# TC_board.net
KiCad netlist of a schematic drawn in EAGLE
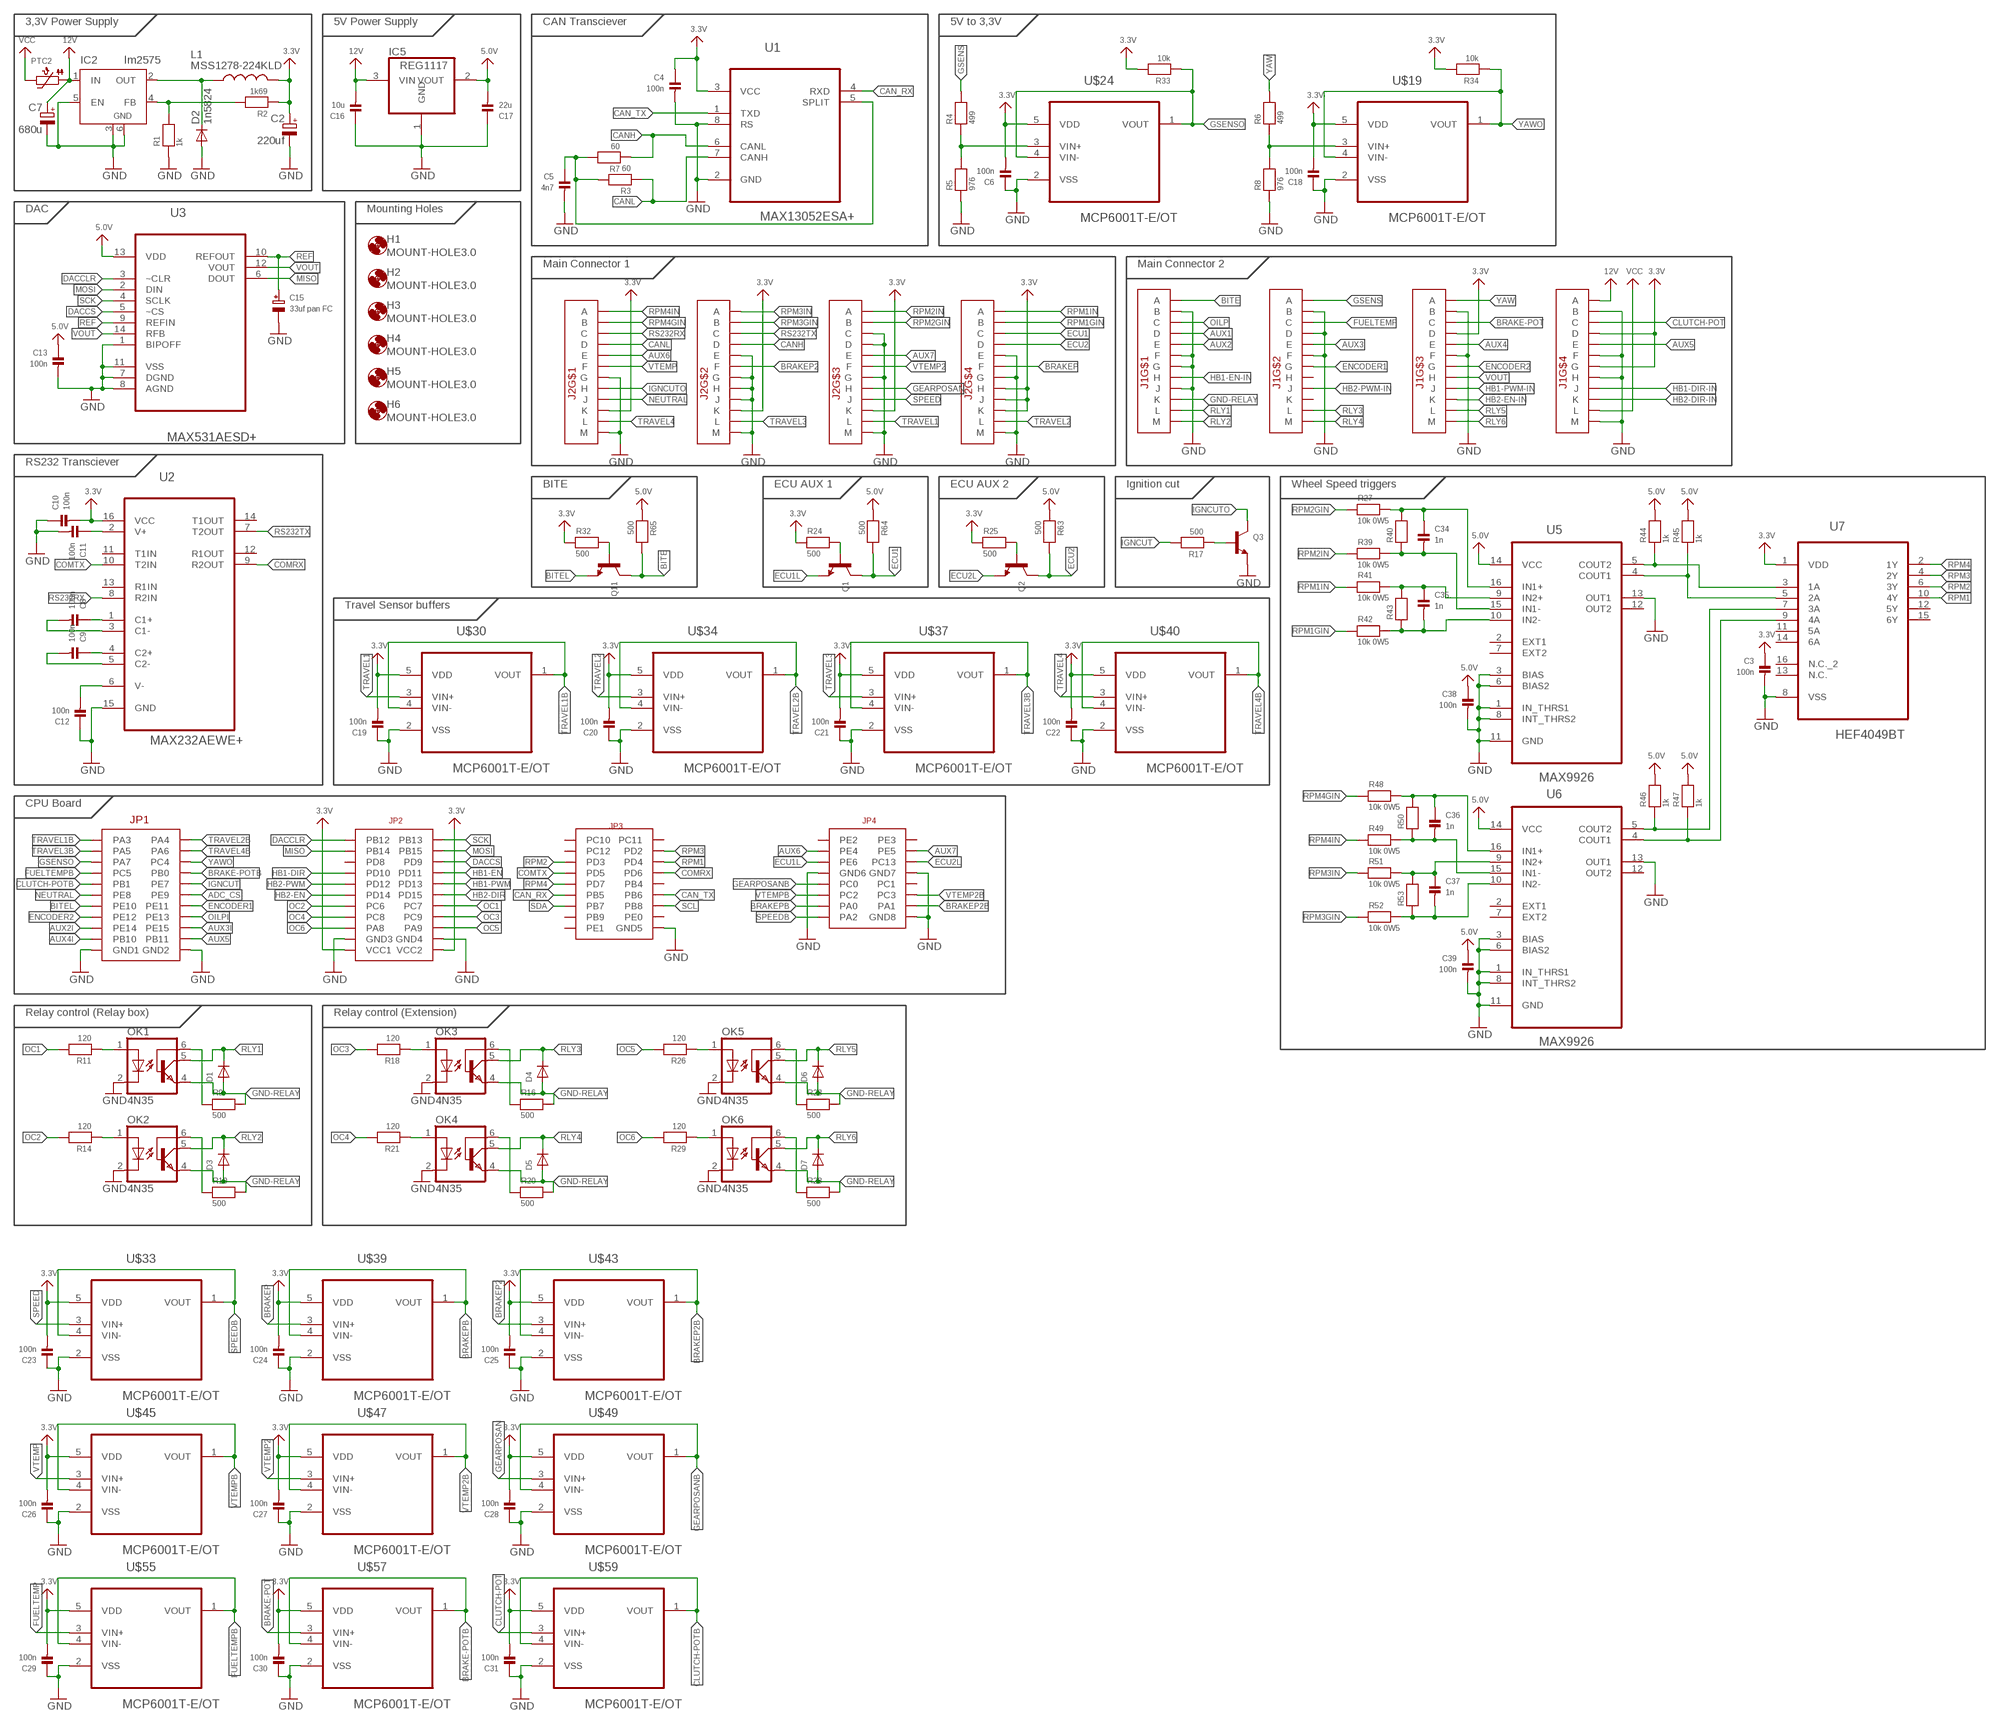
[diagram p0: schematic, sheet 1, part 1 of 2]
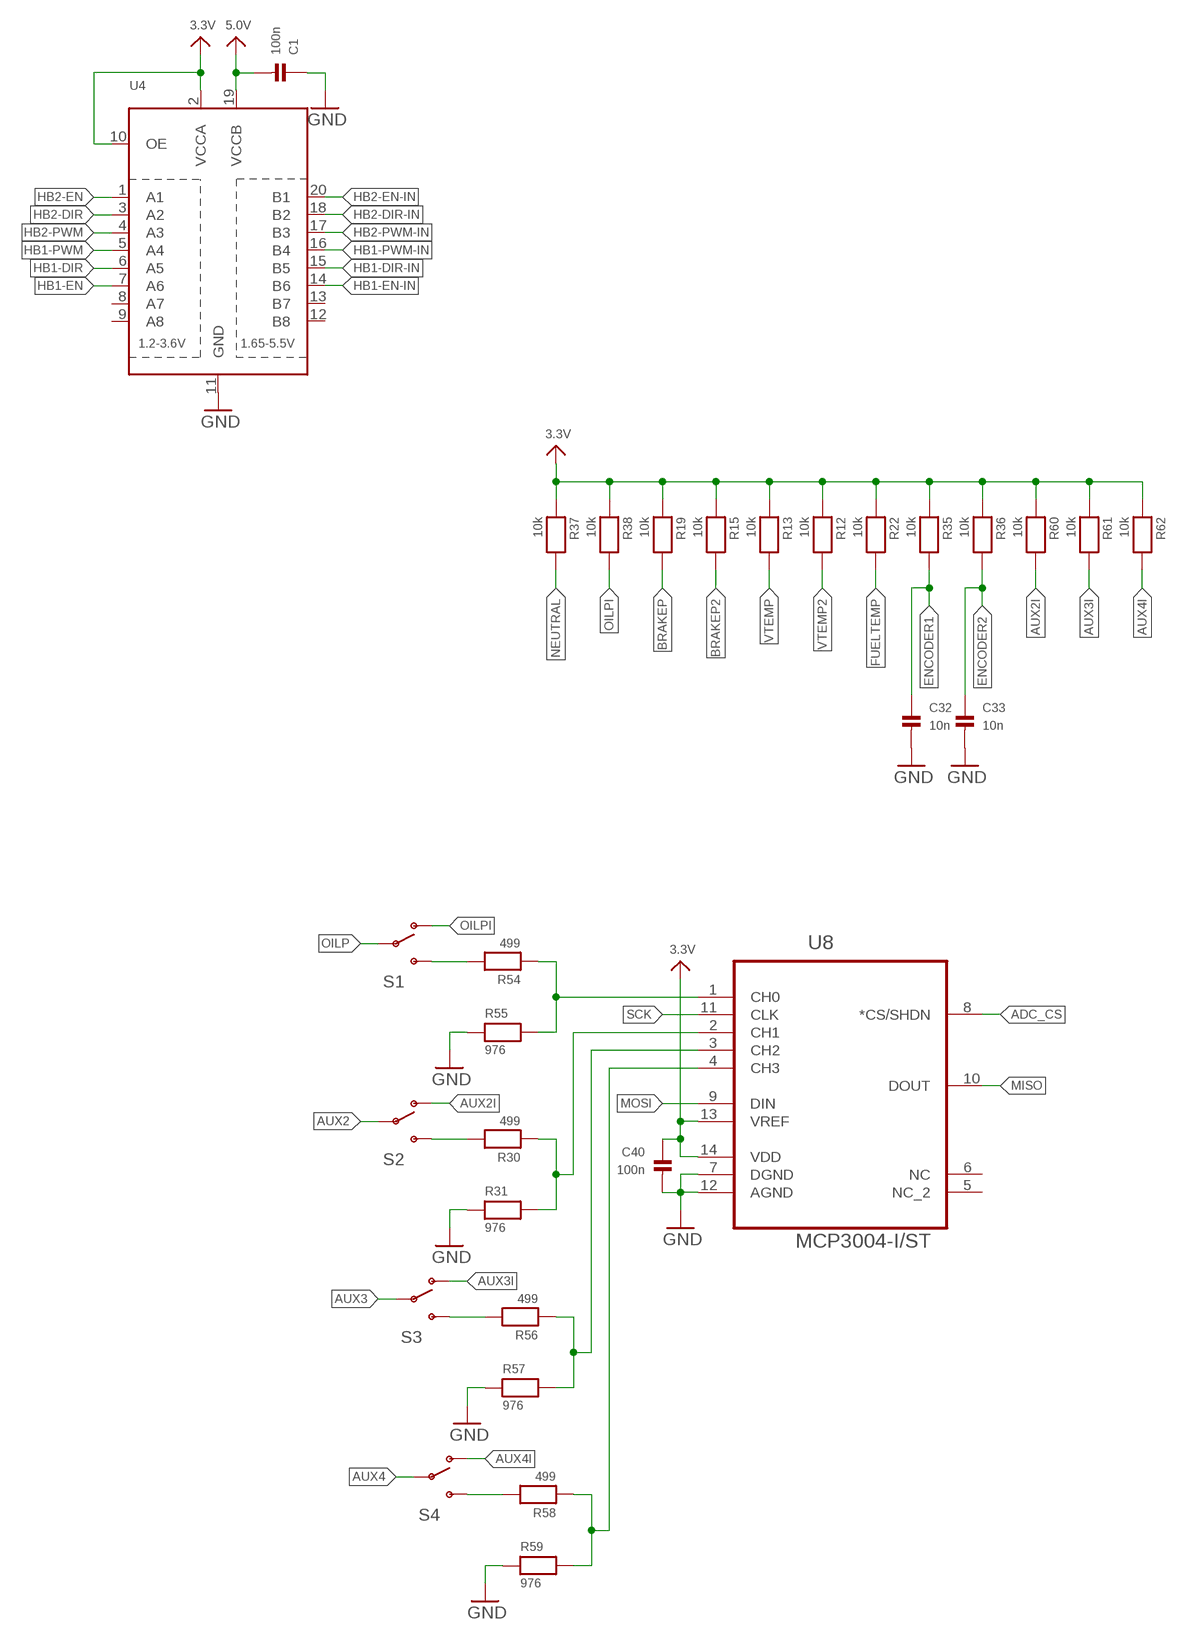
[diagram p1: schematic, sheet 1, part 2 of 2]

(export (version "E")
  (design (tool "Eeschema 10.0.6"))
  (components
    (comp (ref "C1")
      (value "100n")
      (footprint "eagle-import:_0603")
      (libsource (lib "eagle-import") (part "CAP_CERAMIC_0603"))
    )
    (comp (ref "C2")
      (value "220uf")
      (footprint "eagle-import:E3,5-8")
      (libsource (lib "eagle-import") (part "CPOL-EUE3.5-8"))
    )
    (comp (ref "C3")
      (value "100n")
      (footprint "eagle-import:_0603")
      (libsource (lib "eagle-import") (part "CAP_CERAMIC_0603"))
    )
    (comp (ref "C4")
      (value "100n")
      (footprint "eagle-import:_0603")
      (libsource (lib "eagle-import") (part "CAP_CERAMIC_0603"))
    )
    (comp (ref "C5")
      (value "4n7")
      (footprint "eagle-import:_0603")
      (libsource (lib "eagle-import") (part "CAP_CERAMIC_0603"))
    )
    (comp (ref "C6")
      (value "100n")
      (footprint "eagle-import:_0603")
      (libsource (lib "eagle-import") (part "CAP_CERAMIC_0603"))
    )
    (comp (ref "C7")
      (value "680u")
      (footprint "eagle-import:E5-10,5")
      (libsource (lib "eagle-import") (part "CPOL-EUE5-10.5"))
    )
    (comp (ref "C8")
      (value "100n")
      (footprint "eagle-import:_0603")
      (libsource (lib "eagle-import") (part "CAP_CERAMIC_0603"))
    )
    (comp (ref "C9")
      (value "100n")
      (footprint "eagle-import:_0603")
      (libsource (lib "eagle-import") (part "CAP_CERAMIC_0603"))
    )
    (comp (ref "C10")
      (value "100n")
      (footprint "eagle-import:_0603")
      (libsource (lib "eagle-import") (part "CAP_CERAMIC_0603"))
    )
    (comp (ref "C11")
      (value "100n")
      (footprint "eagle-import:_0603")
      (libsource (lib "eagle-import") (part "CAP_CERAMIC_0603"))
    )
    (comp (ref "C12")
      (value "100n")
      (footprint "eagle-import:_0603")
      (libsource (lib "eagle-import") (part "CAP_CERAMIC_0603"))
    )
    (comp (ref "C13")
      (value "100n")
      (footprint "eagle-import:_0603")
      (libsource (lib "eagle-import") (part "CAP_CERAMIC_0603"))
    )
    (comp (ref "C15")
      (value "33uf pan FC")
      (footprint "eagle-import:PANASONIC_D")
      (libsource (lib "eagle-import") (part "CAP_ELECTROLYTICPANASONIC_D"))
    )
    (comp (ref "C16")
      (value "10u")
      (footprint "eagle-import:_0805")
      (libsource (lib "eagle-import") (part "CAP_CERAMIC_0805"))
    )
    (comp (ref "C17")
      (value "22u")
      (footprint "eagle-import:_0805")
      (libsource (lib "eagle-import") (part "CAP_CERAMIC_0805"))
    )
    (comp (ref "C18")
      (value "100n")
      (footprint "eagle-import:_0603")
      (libsource (lib "eagle-import") (part "CAP_CERAMIC_0603"))
    )
    (comp (ref "C19")
      (value "100n")
      (footprint "eagle-import:_0603")
      (libsource (lib "eagle-import") (part "CAP_CERAMIC_0603"))
    )
    (comp (ref "C20")
      (value "100n")
      (footprint "eagle-import:_0603")
      (libsource (lib "eagle-import") (part "CAP_CERAMIC_0603"))
    )
    (comp (ref "C21")
      (value "100n")
      (footprint "eagle-import:_0603")
      (libsource (lib "eagle-import") (part "CAP_CERAMIC_0603"))
    )
    (comp (ref "C22")
      (value "100n")
      (footprint "eagle-import:_0603")
      (libsource (lib "eagle-import") (part "CAP_CERAMIC_0603"))
    )
    (comp (ref "C23")
      (value "100n")
      (footprint "eagle-import:_0603")
      (libsource (lib "eagle-import") (part "CAP_CERAMIC_0603"))
    )
    (comp (ref "C24")
      (value "100n")
      (footprint "eagle-import:_0603")
      (libsource (lib "eagle-import") (part "CAP_CERAMIC_0603"))
    )
    (comp (ref "C25")
      (value "100n")
      (footprint "eagle-import:_0603")
      (libsource (lib "eagle-import") (part "CAP_CERAMIC_0603"))
    )
    (comp (ref "C26")
      (value "100n")
      (footprint "eagle-import:_0603")
      (libsource (lib "eagle-import") (part "CAP_CERAMIC_0603"))
    )
    (comp (ref "C27")
      (value "100n")
      (footprint "eagle-import:_0603")
      (libsource (lib "eagle-import") (part "CAP_CERAMIC_0603"))
    )
    (comp (ref "C28")
      (value "100n")
      (footprint "eagle-import:_0603")
      (libsource (lib "eagle-import") (part "CAP_CERAMIC_0603"))
    )
    (comp (ref "C29")
      (value "100n")
      (footprint "eagle-import:_0603")
      (libsource (lib "eagle-import") (part "CAP_CERAMIC_0603"))
    )
    (comp (ref "C30")
      (value "100n")
      (footprint "eagle-import:_0603")
      (libsource (lib "eagle-import") (part "CAP_CERAMIC_0603"))
    )
    (comp (ref "C31")
      (value "100n")
      (footprint "eagle-import:_0603")
      (libsource (lib "eagle-import") (part "CAP_CERAMIC_0603"))
    )
    (comp (ref "C32")
      (value "10n")
      (footprint "eagle-import:_0603")
      (libsource (lib "eagle-import") (part "CAP_CERAMIC_0603"))
    )
    (comp (ref "C33")
      (value "10n")
      (footprint "eagle-import:_0603")
      (libsource (lib "eagle-import") (part "CAP_CERAMIC_0603"))
    )
    (comp (ref "C34")
      (value "1n")
      (footprint "eagle-import:_0603")
      (libsource (lib "eagle-import") (part "CAP_CERAMIC_0603"))
    )
    (comp (ref "C35")
      (value "1n")
      (footprint "eagle-import:_0603")
      (libsource (lib "eagle-import") (part "CAP_CERAMIC_0603"))
    )
    (comp (ref "C36")
      (value "1n")
      (footprint "eagle-import:_0603")
      (libsource (lib "eagle-import") (part "CAP_CERAMIC_0603"))
    )
    (comp (ref "C37")
      (value "1n")
      (footprint "eagle-import:_0603")
      (libsource (lib "eagle-import") (part "CAP_CERAMIC_0603"))
    )
    (comp (ref "C38")
      (value "100n")
      (footprint "eagle-import:_0603")
      (libsource (lib "eagle-import") (part "CAP_CERAMIC_0603"))
    )
    (comp (ref "C39")
      (value "100n")
      (footprint "eagle-import:_0603")
      (libsource (lib "eagle-import") (part "CAP_CERAMIC_0603"))
    )
    (comp (ref "C40")
      (value "100n")
      (footprint "eagle-import:_0603")
      (libsource (lib "eagle-import") (part "CAP_CERAMIC_0603"))
    )
    (comp (ref "D1")
      (value "DIODESOD-323F")
      (footprint "eagle-import:SOD-323F")
      (libsource (lib "eagle-import") (part "DIODESOD-323F"))
    )
    (comp (ref "D2")
      (value "1n5824")
      (footprint "eagle-import:DO201-15")
      (libsource (lib "eagle-import") (part "1N5400"))
    )
    (comp (ref "D3")
      (value "DIODESOD-323F")
      (footprint "eagle-import:SOD-323F")
      (libsource (lib "eagle-import") (part "DIODESOD-323F"))
    )
    (comp (ref "D4")
      (value "DIODESOD-323F")
      (footprint "eagle-import:SOD-323F")
      (libsource (lib "eagle-import") (part "DIODESOD-323F"))
    )
    (comp (ref "D5")
      (value "DIODESOD-323F")
      (footprint "eagle-import:SOD-323F")
      (libsource (lib "eagle-import") (part "DIODESOD-323F"))
    )
    (comp (ref "D6")
      (value "DIODESOD-323F")
      (footprint "eagle-import:SOD-323F")
      (libsource (lib "eagle-import") (part "DIODESOD-323F"))
    )
    (comp (ref "D7")
      (value "DIODESOD-323F")
      (footprint "eagle-import:SOD-323F")
      (libsource (lib "eagle-import") (part "DIODESOD-323F"))
    )
    (comp (ref "H1")
      (value "MOUNT-HOLE3.0")
      (footprint "eagle-import:3,0")
      (libsource (lib "eagle-import") (part "MOUNT-HOLE3.0"))
    )
    (comp (ref "H2")
      (value "MOUNT-HOLE3.0")
      (footprint "eagle-import:3,0")
      (libsource (lib "eagle-import") (part "MOUNT-HOLE3.0"))
    )
    (comp (ref "H3")
      (value "MOUNT-HOLE3.0")
      (footprint "eagle-import:3,0")
      (libsource (lib "eagle-import") (part "MOUNT-HOLE3.0"))
    )
    (comp (ref "H4")
      (value "MOUNT-HOLE3.0")
      (footprint "eagle-import:3,0")
      (libsource (lib "eagle-import") (part "MOUNT-HOLE3.0"))
    )
    (comp (ref "H5")
      (value "MOUNT-HOLE3.0")
      (footprint "eagle-import:3,0")
      (libsource (lib "eagle-import") (part "MOUNT-HOLE3.0"))
    )
    (comp (ref "H6")
      (value "MOUNT-HOLE3.0")
      (footprint "eagle-import:3,0")
      (libsource (lib "eagle-import") (part "MOUNT-HOLE3.0"))
    )
    (comp (ref "IC2")
      (value "lm2575")
      (footprint "eagle-import:TO263-5")
      (libsource (lib "eagle-import") (part "LM2596S"))
    )
    (comp (ref "IC5")
      (value "REG1117")
      (footprint "eagle-import:SOT223")
      (libsource (lib "eagle-import") (part "REG1117"))
    )
    (comp (ref "J1")
      (value "CON1")
      (footprint "eagle-import:AUTOCONNECTOR")
      (libsource (lib "eagle-import") (part "AUTOCONNECTOR"))
    )
    (comp (ref "J2")
      (value "CON1")
      (footprint "eagle-import:AUTOCONNECTOR")
      (libsource (lib "eagle-import") (part "AUTOCONNECTOR"))
    )
    (comp (ref "L1")
      (value "MSS1278-224KLD")
      (footprint "eagle-import:CDRH125")
      (libsource (lib "eagle-import") (part "INDUCTORPWR"))
    )
    (comp (ref "OK1")
      (value "4N35")
      (footprint "eagle-import:DIL06")
      (fields (field (name "MF") "FAIRCHILD SEMICONDUCTOR"))
      (libsource (lib "eagle-import") (part "4N35"))
    )
    (comp (ref "OK2")
      (value "4N35")
      (footprint "eagle-import:DIL06")
      (fields (field (name "MF") "FAIRCHILD SEMICONDUCTOR"))
      (libsource (lib "eagle-import") (part "4N35"))
    )
    (comp (ref "OK3")
      (value "4N35")
      (footprint "eagle-import:DIL06")
      (fields (field (name "MF") "FAIRCHILD SEMICONDUCTOR"))
      (libsource (lib "eagle-import") (part "4N35"))
    )
    (comp (ref "OK4")
      (value "4N35")
      (footprint "eagle-import:DIL06")
      (fields (field (name "MF") "FAIRCHILD SEMICONDUCTOR"))
      (libsource (lib "eagle-import") (part "4N35"))
    )
    (comp (ref "OK5")
      (value "4N35")
      (footprint "eagle-import:DIL06")
      (fields (field (name "MF") "FAIRCHILD SEMICONDUCTOR"))
      (libsource (lib "eagle-import") (part "4N35"))
    )
    (comp (ref "OK6")
      (value "4N35")
      (footprint "eagle-import:DIL06")
      (fields (field (name "MF") "FAIRCHILD SEMICONDUCTOR"))
      (libsource (lib "eagle-import") (part "4N35"))
    )
    (comp (ref "PTC2")
      (value "PTC1812")
      (footprint "eagle-import:PTC1812")
      (libsource (lib "eagle-import") (part "PTC1812"))
    )
    (comp (ref "Q1")
      (value "TRANSISTOR_NPNWIDE")
      (footprint "eagle-import:SOT23-WIDE")
      (libsource (lib "eagle-import") (part "TRANSISTOR_NPNWIDE"))
    )
    (comp (ref "Q2")
      (value "TRANSISTOR_NPNWIDE")
      (footprint "eagle-import:SOT23-WIDE")
      (libsource (lib "eagle-import") (part "TRANSISTOR_NPNWIDE"))
    )
    (comp (ref "Q3")
      (value "TRANSISTOR_NPNWIDE")
      (footprint "eagle-import:SOT23-WIDE")
      (libsource (lib "eagle-import") (part "TRANSISTOR_NPNWIDE"))
    )
    (comp (ref "Q11")
      (value "TRANSISTOR_NPNWIDE")
      (footprint "eagle-import:SOT23-WIDE")
      (libsource (lib "eagle-import") (part "TRANSISTOR_NPNWIDE"))
    )
    (comp (ref "R1")
      (value "1k")
      (footprint "eagle-import:_0603")
      (libsource (lib "eagle-import") (part "RESISTOR_0603"))
    )
    (comp (ref "R2")
      (value "1k69")
      (footprint "eagle-import:_0603")
      (libsource (lib "eagle-import") (part "RESISTOR_0603"))
    )
    (comp (ref "R3")
      (value "60")
      (footprint "eagle-import:_0603")
      (libsource (lib "eagle-import") (part "RESISTOR_0603"))
    )
    (comp (ref "R4")
      (value "499")
      (footprint "eagle-import:_0603")
      (libsource (lib "eagle-import") (part "RESISTOR_0603"))
    )
    (comp (ref "R5")
      (value "976")
      (footprint "eagle-import:_0603")
      (libsource (lib "eagle-import") (part "RESISTOR_0603"))
    )
    (comp (ref "R6")
      (value "499")
      (footprint "eagle-import:_0603")
      (libsource (lib "eagle-import") (part "RESISTOR_0603"))
    )
    (comp (ref "R7")
      (value "60")
      (footprint "eagle-import:_0603")
      (libsource (lib "eagle-import") (part "RESISTOR_0603"))
    )
    (comp (ref "R8")
      (value "976")
      (footprint "eagle-import:_0603")
      (libsource (lib "eagle-import") (part "RESISTOR_0603"))
    )
    (comp (ref "R9")
      (value "500")
      (footprint "eagle-import:_0603")
      (libsource (lib "eagle-import") (part "RESISTOR_0603"))
    )
    (comp (ref "R10")
      (value "500")
      (footprint "eagle-import:_0603")
      (libsource (lib "eagle-import") (part "RESISTOR_0603"))
    )
    (comp (ref "R11")
      (value "120")
      (footprint "eagle-import:_0603")
      (libsource (lib "eagle-import") (part "RESISTOR_0603"))
    )
    (comp (ref "R12")
      (value "10k")
      (footprint "eagle-import:_0603")
      (libsource (lib "eagle-import") (part "RESISTOR_0603"))
    )
    (comp (ref "R13")
      (value "10k")
      (footprint "eagle-import:_0603")
      (libsource (lib "eagle-import") (part "RESISTOR_0603"))
    )
    (comp (ref "R14")
      (value "120")
      (footprint "eagle-import:_0603")
      (libsource (lib "eagle-import") (part "RESISTOR_0603"))
    )
    (comp (ref "R15")
      (value "10k")
      (footprint "eagle-import:_0603")
      (libsource (lib "eagle-import") (part "RESISTOR_0603"))
    )
    (comp (ref "R16")
      (value "500")
      (footprint "eagle-import:_0603")
      (libsource (lib "eagle-import") (part "RESISTOR_0603"))
    )
    (comp (ref "R17")
      (value "500")
      (footprint "eagle-import:_0603")
      (libsource (lib "eagle-import") (part "RESISTOR_0603"))
    )
    (comp (ref "R18")
      (value "120")
      (footprint "eagle-import:_0603")
      (libsource (lib "eagle-import") (part "RESISTOR_0603"))
    )
    (comp (ref "R19")
      (value "10k")
      (footprint "eagle-import:_0603")
      (libsource (lib "eagle-import") (part "RESISTOR_0603"))
    )
    (comp (ref "R20")
      (value "500")
      (footprint "eagle-import:_0603")
      (libsource (lib "eagle-import") (part "RESISTOR_0603"))
    )
    (comp (ref "R21")
      (value "120")
      (footprint "eagle-import:_0603")
      (libsource (lib "eagle-import") (part "RESISTOR_0603"))
    )
    (comp (ref "R22")
      (value "10k")
      (footprint "eagle-import:_0603")
      (libsource (lib "eagle-import") (part "RESISTOR_0603"))
    )
    (comp (ref "R23")
      (value "500")
      (footprint "eagle-import:_0603")
      (libsource (lib "eagle-import") (part "RESISTOR_0603"))
    )
    (comp (ref "R24")
      (value "500")
      (footprint "eagle-import:_0603")
      (libsource (lib "eagle-import") (part "RESISTOR_0603"))
    )
    (comp (ref "R25")
      (value "500")
      (footprint "eagle-import:_0603")
      (libsource (lib "eagle-import") (part "RESISTOR_0603"))
    )
    (comp (ref "R26")
      (value "120")
      (footprint "eagle-import:_0603")
      (libsource (lib "eagle-import") (part "RESISTOR_0603"))
    )
    (comp (ref "R27")
      (value "10k 0W5")
      (footprint "eagle-import:_0805")
      (libsource (lib "eagle-import") (part "RESISTOR_0805"))
    )
    (comp (ref "R28")
      (value "500")
      (footprint "eagle-import:_0603")
      (libsource (lib "eagle-import") (part "RESISTOR_0603"))
    )
    (comp (ref "R29")
      (value "120")
      (footprint "eagle-import:_0603")
      (libsource (lib "eagle-import") (part "RESISTOR_0603"))
    )
    (comp (ref "R30")
      (value "499")
      (footprint "eagle-import:_0603")
      (libsource (lib "eagle-import") (part "RESISTOR_0603"))
    )
    (comp (ref "R31")
      (value "976")
      (footprint "eagle-import:_0603")
      (libsource (lib "eagle-import") (part "RESISTOR_0603"))
    )
    (comp (ref "R32")
      (value "500")
      (footprint "eagle-import:_0603")
      (libsource (lib "eagle-import") (part "RESISTOR_0603"))
    )
    (comp (ref "R33")
      (value "10k")
      (footprint "eagle-import:_0603")
      (libsource (lib "eagle-import") (part "RESISTOR_0603"))
    )
    (comp (ref "R34")
      (value "10k")
      (footprint "eagle-import:_0603")
      (libsource (lib "eagle-import") (part "RESISTOR_0603"))
    )
    (comp (ref "R35")
      (value "10k")
      (footprint "eagle-import:_0603")
      (libsource (lib "eagle-import") (part "RESISTOR_0603"))
    )
    (comp (ref "R36")
      (value "10k")
      (footprint "eagle-import:_0603")
      (libsource (lib "eagle-import") (part "RESISTOR_0603"))
    )
    (comp (ref "R37")
      (value "10k")
      (footprint "eagle-import:_0603")
      (libsource (lib "eagle-import") (part "RESISTOR_0603"))
    )
    (comp (ref "R38")
      (value "10k")
      (footprint "eagle-import:_0603")
      (libsource (lib "eagle-import") (part "RESISTOR_0603"))
    )
    (comp (ref "R39")
      (value "10k 0W5")
      (footprint "eagle-import:_0805")
      (libsource (lib "eagle-import") (part "RESISTOR_0805"))
    )
    (comp (ref "R40")
      (value "RESISTOR_0805")
      (footprint "eagle-import:_0805")
      (libsource (lib "eagle-import") (part "RESISTOR_0805"))
    )
    (comp (ref "R41")
      (value "10k 0W5")
      (footprint "eagle-import:_0805")
      (libsource (lib "eagle-import") (part "RESISTOR_0805"))
    )
    (comp (ref "R42")
      (value "10k 0W5")
      (footprint "eagle-import:_0805")
      (libsource (lib "eagle-import") (part "RESISTOR_0805"))
    )
    (comp (ref "R43")
      (value "RESISTOR_0805")
      (footprint "eagle-import:_0805")
      (libsource (lib "eagle-import") (part "RESISTOR_0805"))
    )
    (comp (ref "R44")
      (value "1k")
      (footprint "eagle-import:_0603")
      (libsource (lib "eagle-import") (part "RESISTOR_0603"))
    )
    (comp (ref "R45")
      (value "1k")
      (footprint "eagle-import:_0603")
      (libsource (lib "eagle-import") (part "RESISTOR_0603"))
    )
    (comp (ref "R46")
      (value "1k")
      (footprint "eagle-import:_0603")
      (libsource (lib "eagle-import") (part "RESISTOR_0603"))
    )
    (comp (ref "R47")
      (value "1k")
      (footprint "eagle-import:_0603")
      (libsource (lib "eagle-import") (part "RESISTOR_0603"))
    )
    (comp (ref "R48")
      (value "10k 0W5")
      (footprint "eagle-import:_0805")
      (libsource (lib "eagle-import") (part "RESISTOR_0805"))
    )
    (comp (ref "R49")
      (value "10k 0W5")
      (footprint "eagle-import:_0805")
      (libsource (lib "eagle-import") (part "RESISTOR_0805"))
    )
    (comp (ref "R50")
      (value "RESISTOR_0805")
      (footprint "eagle-import:_0805")
      (libsource (lib "eagle-import") (part "RESISTOR_0805"))
    )
    (comp (ref "R51")
      (value "10k 0W5")
      (footprint "eagle-import:_0805")
      (libsource (lib "eagle-import") (part "RESISTOR_0805"))
    )
    (comp (ref "R52")
      (value "10k 0W5")
      (footprint "eagle-import:_0805")
      (libsource (lib "eagle-import") (part "RESISTOR_0805"))
    )
    (comp (ref "R53")
      (value "RESISTOR_0805")
      (footprint "eagle-import:_0805")
      (libsource (lib "eagle-import") (part "RESISTOR_0805"))
    )
    (comp (ref "R54")
      (value "499")
      (footprint "eagle-import:_0603")
      (libsource (lib "eagle-import") (part "RESISTOR_0603"))
    )
    (comp (ref "R55")
      (value "976")
      (footprint "eagle-import:_0603")
      (libsource (lib "eagle-import") (part "RESISTOR_0603"))
    )
    (comp (ref "R56")
      (value "499")
      (footprint "eagle-import:_0603")
      (libsource (lib "eagle-import") (part "RESISTOR_0603"))
    )
    (comp (ref "R57")
      (value "976")
      (footprint "eagle-import:_0603")
      (libsource (lib "eagle-import") (part "RESISTOR_0603"))
    )
    (comp (ref "R58")
      (value "499")
      (footprint "eagle-import:_0603")
      (libsource (lib "eagle-import") (part "RESISTOR_0603"))
    )
    (comp (ref "R59")
      (value "976")
      (footprint "eagle-import:_0603")
      (libsource (lib "eagle-import") (part "RESISTOR_0603"))
    )
    (comp (ref "R60")
      (value "10k")
      (footprint "eagle-import:_0603")
      (libsource (lib "eagle-import") (part "RESISTOR_0603"))
    )
    (comp (ref "R61")
      (value "10k")
      (footprint "eagle-import:_0603")
      (libsource (lib "eagle-import") (part "RESISTOR_0603"))
    )
    (comp (ref "R62")
      (value "10k")
      (footprint "eagle-import:_0603")
      (libsource (lib "eagle-import") (part "RESISTOR_0603"))
    )
    (comp (ref "R63")
      (value "500")
      (footprint "eagle-import:_0603")
      (libsource (lib "eagle-import") (part "RESISTOR_0603"))
    )
    (comp (ref "R64")
      (value "500")
      (footprint "eagle-import:_0603")
      (libsource (lib "eagle-import") (part "RESISTOR_0603"))
    )
    (comp (ref "R65")
      (value "500")
      (footprint "eagle-import:_0603")
      (libsource (lib "eagle-import") (part "RESISTOR_0603"))
    )
    (comp (ref "S1")
      (value "SWITCH-SPDT-SMD-A")
      (footprint "eagle-import:SWITCH-SPST-SMD-A")
      (libsource (lib "eagle-import") (part "SWITCH-SPDT-SMD-A"))
    )
    (comp (ref "S2")
      (value "SWITCH-SPDT-SMD-A")
      (footprint "eagle-import:SWITCH-SPST-SMD-A")
      (libsource (lib "eagle-import") (part "SWITCH-SPDT-SMD-A"))
    )
    (comp (ref "S3")
      (value "SWITCH-SPDT-SMD-A")
      (footprint "eagle-import:SWITCH-SPST-SMD-A")
      (libsource (lib "eagle-import") (part "SWITCH-SPDT-SMD-A"))
    )
    (comp (ref "S4")
      (value "SWITCH-SPDT-SMD-A")
      (footprint "eagle-import:SWITCH-SPST-SMD-A")
      (libsource (lib "eagle-import") (part "SWITCH-SPDT-SMD-A"))
    )
    (comp (ref "U$1")
      (value "CPU-BOARD")
      (footprint "eagle-import:CPU-BOARD-JP1")
      (libsource (lib "eagle-import") (part "CPU-BOARD"))
    )
    (comp (ref "U$19")
      (value "MCP6001T-E/OT")
      (footprint "eagle-import:SOT95P270X145-5N")
      (libsource (lib "eagle-import") (part "MCP6001T-E/OT"))
    )
    (comp (ref "U$24")
      (value "MCP6001T-E/OT")
      (footprint "eagle-import:SOT95P270X145-5N")
      (libsource (lib "eagle-import") (part "MCP6001T-E/OT"))
    )
    (comp (ref "U$30")
      (value "MCP6001T-E/OT")
      (footprint "eagle-import:SOT95P270X145-5N")
      (libsource (lib "eagle-import") (part "MCP6001T-E/OT"))
    )
    (comp (ref "U$33")
      (value "MCP6001T-E/OT")
      (footprint "eagle-import:SOT95P270X145-5N")
      (libsource (lib "eagle-import") (part "MCP6001T-E/OT"))
    )
    (comp (ref "U$34")
      (value "MCP6001T-E/OT")
      (footprint "eagle-import:SOT95P270X145-5N")
      (libsource (lib "eagle-import") (part "MCP6001T-E/OT"))
    )
    (comp (ref "U$37")
      (value "MCP6001T-E/OT")
      (footprint "eagle-import:SOT95P270X145-5N")
      (libsource (lib "eagle-import") (part "MCP6001T-E/OT"))
    )
    (comp (ref "U$39")
      (value "MCP6001T-E/OT")
      (footprint "eagle-import:SOT95P270X145-5N")
      (libsource (lib "eagle-import") (part "MCP6001T-E/OT"))
    )
    (comp (ref "U$40")
      (value "MCP6001T-E/OT")
      (footprint "eagle-import:SOT95P270X145-5N")
      (libsource (lib "eagle-import") (part "MCP6001T-E/OT"))
    )
    (comp (ref "U$43")
      (value "MCP6001T-E/OT")
      (footprint "eagle-import:SOT95P270X145-5N")
      (libsource (lib "eagle-import") (part "MCP6001T-E/OT"))
    )
    (comp (ref "U$45")
      (value "MCP6001T-E/OT")
      (footprint "eagle-import:SOT95P270X145-5N")
      (libsource (lib "eagle-import") (part "MCP6001T-E/OT"))
    )
    (comp (ref "U$47")
      (value "MCP6001T-E/OT")
      (footprint "eagle-import:SOT95P270X145-5N")
      (libsource (lib "eagle-import") (part "MCP6001T-E/OT"))
    )
    (comp (ref "U$49")
      (value "MCP6001T-E/OT")
      (footprint "eagle-import:SOT95P270X145-5N")
      (libsource (lib "eagle-import") (part "MCP6001T-E/OT"))
    )
    (comp (ref "U$55")
      (value "MCP6001T-E/OT")
      (footprint "eagle-import:SOT95P270X145-5N")
      (libsource (lib "eagle-import") (part "MCP6001T-E/OT"))
    )
    (comp (ref "U$57")
      (value "MCP6001T-E/OT")
      (footprint "eagle-import:SOT95P270X145-5N")
      (libsource (lib "eagle-import") (part "MCP6001T-E/OT"))
    )
    (comp (ref "U$59")
      (value "MCP6001T-E/OT")
      (footprint "eagle-import:SOT95P270X145-5N")
      (libsource (lib "eagle-import") (part "MCP6001T-E/OT"))
    )
    (comp (ref "U1")
      (value "MAX13052ESA+")
      (footprint "eagle-import:SOIC127P600X175-8N")
      (libsource (lib "eagle-import") (part "MAX13052ESA+"))
    )
    (comp (ref "U2")
      (value "MAX232AEWE+")
      (footprint "eagle-import:SOIC127P1032X265-16N")
      (libsource (lib "eagle-import") (part "MAX232AEWE+"))
    )
    (comp (ref "U3")
      (value "MAX531AESD+")
      (footprint "eagle-import:SOIC127P600X175-14N")
      (libsource (lib "eagle-import") (part "MAX531AESD+"))
    )
    (comp (ref "U4")
      (value "TXB0108PWR")
      (footprint "eagle-import:TSSOP20")
      (libsource (lib "eagle-import") (part "TXB0108PWR"))
    )
    (comp (ref "U5")
      (value "MAX9926")
      (footprint "eagle-import:SOP63P600X175-16N")
      (fields (field (name "MPN") "MAX9927AEE+"))
      (libsource (lib "eagle-import") (part "MAX9927AEE+"))
    )
    (comp (ref "U6")
      (value "MAX9926")
      (footprint "eagle-import:SOP63P600X175-16N")
      (fields (field (name "MPN") "MAX9927AEE+"))
      (libsource (lib "eagle-import") (part "MAX9927AEE+"))
    )
    (comp (ref "U7")
      (value "HEF4049BT")
      (footprint "eagle-import:SOIC127P600X175-16N")
      (libsource (lib "eagle-import") (part "HEF4049BT"))
    )
    (comp (ref "U8")
      (value "MCP3004-I/ST")
      (footprint "eagle-import:SOP65P640X120-14N")
      (libsource (lib "eagle-import") (part "MCP3004-I/ST"))
    )
  )
  (nets
    (net (code "1") (name "3.3V") (class "Default")
      (node (ref "C10") (pin "2") (pinfunction "P$2_2") (pintype "passive"))
      (node (ref "C18") (pin "2") (pinfunction "P$2_2") (pintype "passive"))
      (node (ref "C19") (pin "2") (pinfunction "P$2_2") (pintype "passive"))
      (node (ref "C2") (pin "+") (pinfunction "+_+") (pintype "passive"))
      (node (ref "C20") (pin "2") (pinfunction "P$2_2") (pintype "passive"))
      (node (ref "C21") (pin "2") (pinfunction "P$2_2") (pintype "passive"))
      (node (ref "C22") (pin "2") (pinfunction "P$2_2") (pintype "passive"))
      (node (ref "C23") (pin "2") (pinfunction "P$2_2") (pintype "passive"))
      (node (ref "C24") (pin "2") (pinfunction "P$2_2") (pintype "passive"))
      (node (ref "C25") (pin "2") (pinfunction "P$2_2") (pintype "passive"))
      (node (ref "C26") (pin "2") (pinfunction "P$2_2") (pintype "passive"))
      (node (ref "C27") (pin "2") (pinfunction "P$2_2") (pintype "passive"))
      (node (ref "C28") (pin "2") (pinfunction "P$2_2") (pintype "passive"))
      (node (ref "C29") (pin "2") (pinfunction "P$2_2") (pintype "passive"))
      (node (ref "C3") (pin "1") (pinfunction "P$1_1") (pintype "passive"))
      (node (ref "C30") (pin "2") (pinfunction "P$2_2") (pintype "passive"))
      (node (ref "C31") (pin "2") (pinfunction "P$2_2") (pintype "passive"))
      (node (ref "C4") (pin "1") (pinfunction "P$1_1") (pintype "passive"))
      (node (ref "C40") (pin "1") (pinfunction "P$1_1") (pintype "passive"))
      (node (ref "C6") (pin "2") (pinfunction "P$2_2") (pintype "passive"))
      (node (ref "J1") (pin "D3") (pinfunction "D_D3") (pintype "bidirectional"))
      (node (ref "J1") (pin "D4") (pinfunction "D_D4") (pintype "bidirectional"))
      (node (ref "J1") (pin "G4") (pinfunction "G_G4") (pintype "bidirectional"))
      (node (ref "J2") (pin "H4") (pinfunction "H_H4") (pintype "bidirectional"))
      (node (ref "J2") (pin "J4") (pinfunction "J_J4") (pintype "bidirectional"))
      (node (ref "J2") (pin "K1") (pinfunction "K_K1") (pintype "bidirectional"))
      (node (ref "J2") (pin "K2") (pinfunction "K_K2") (pintype "bidirectional"))
      (node (ref "J2") (pin "K3") (pinfunction "K_K3") (pintype "bidirectional"))
      (node (ref "J2") (pin "K4") (pinfunction "K_K4") (pintype "bidirectional"))
      (node (ref "L1") (pin "2") (pinfunction "2_2") (pintype "passive"))
      (node (ref "R12") (pin "1") (pinfunction "1_1") (pintype "passive"))
      (node (ref "R13") (pin "1") (pinfunction "1_1") (pintype "passive"))
      (node (ref "R15") (pin "1") (pinfunction "1_1") (pintype "passive"))
      (node (ref "R19") (pin "1") (pinfunction "1_1") (pintype "passive"))
      (node (ref "R2") (pin "1") (pinfunction "1_1") (pintype "passive"))
      (node (ref "R22") (pin "1") (pinfunction "1_1") (pintype "passive"))
      (node (ref "R24") (pin "1") (pinfunction "1_1") (pintype "passive"))
      (node (ref "R25") (pin "1") (pinfunction "1_1") (pintype "passive"))
      (node (ref "R32") (pin "1") (pinfunction "1_1") (pintype "passive"))
      (node (ref "R33") (pin "2") (pinfunction "2_2") (pintype "passive"))
      (node (ref "R34") (pin "2") (pinfunction "2_2") (pintype "passive"))
      (node (ref "R35") (pin "1") (pinfunction "1_1") (pintype "passive"))
      (node (ref "R36") (pin "1") (pinfunction "1_1") (pintype "passive"))
      (node (ref "R37") (pin "1") (pinfunction "1_1") (pintype "passive"))
      (node (ref "R38") (pin "1") (pinfunction "1_1") (pintype "passive"))
      (node (ref "R60") (pin "1") (pinfunction "1_1") (pintype "passive"))
      (node (ref "R61") (pin "1") (pinfunction "1_1") (pintype "passive"))
      (node (ref "R62") (pin "1") (pinfunction "1_1") (pintype "passive"))
      (node (ref "U$1") (pin "P$43") (pinfunction "VCC1_P$43") (pintype "bidirectional"))
      (node (ref "U$1") (pin "P$44") (pinfunction "VCC2_P$44") (pintype "bidirectional"))
      (node (ref "U$19") (pin "5") (pinfunction "VDD_5") (pintype "power_in"))
      (node (ref "U$24") (pin "5") (pinfunction "VDD_5") (pintype "power_in"))
      (node (ref "U$30") (pin "5") (pinfunction "VDD_5") (pintype "power_in"))
      (node (ref "U$33") (pin "5") (pinfunction "VDD_5") (pintype "power_in"))
      (node (ref "U$34") (pin "5") (pinfunction "VDD_5") (pintype "power_in"))
      (node (ref "U$37") (pin "5") (pinfunction "VDD_5") (pintype "power_in"))
      (node (ref "U$39") (pin "5") (pinfunction "VDD_5") (pintype "power_in"))
      (node (ref "U$40") (pin "5") (pinfunction "VDD_5") (pintype "power_in"))
      (node (ref "U$43") (pin "5") (pinfunction "VDD_5") (pintype "power_in"))
      (node (ref "U$45") (pin "5") (pinfunction "VDD_5") (pintype "power_in"))
      (node (ref "U$47") (pin "5") (pinfunction "VDD_5") (pintype "power_in"))
      (node (ref "U$49") (pin "5") (pinfunction "VDD_5") (pintype "power_in"))
      (node (ref "U$55") (pin "5") (pinfunction "VDD_5") (pintype "power_in"))
      (node (ref "U$57") (pin "5") (pinfunction "VDD_5") (pintype "power_in"))
      (node (ref "U$59") (pin "5") (pinfunction "VDD_5") (pintype "power_in"))
      (node (ref "U1") (pin "3") (pinfunction "VCC_3") (pintype "power_in"))
      (node (ref "U2") (pin "16") (pinfunction "VCC_16") (pintype "power_in"))
      (node (ref "U4") (pin "10") (pinfunction "OE_10") (pintype "bidirectional"))
      (node (ref "U4") (pin "2") (pinfunction "VCCA_2") (pintype "bidirectional"))
      (node (ref "U7") (pin "1") (pinfunction "VDD_1") (pintype "power_in"))
      (node (ref "U8") (pin "13") (pinfunction "VREF_13") (pintype "input"))
      (node (ref "U8") (pin "14") (pinfunction "VDD_14") (pintype "power_in"))
    )
    (net (code "2") (name "5.0V") (class "Default")
      (node (ref "C1") (pin "2") (pinfunction "P$2_2") (pintype "passive"))
      (node (ref "C13") (pin "1") (pinfunction "P$1_1") (pintype "passive"))
      (node (ref "C17") (pin "2") (pinfunction "P$2_2") (pintype "passive"))
      (node (ref "C38") (pin "1") (pinfunction "P$1_1") (pintype "passive"))
      (node (ref "C39") (pin "1") (pinfunction "P$1_1") (pintype "passive"))
      (node (ref "IC5") (pin "2") (pinfunction "VOUT_2") (pintype "output"))
      (node (ref "R44") (pin "2") (pinfunction "2_2") (pintype "passive"))
      (node (ref "R45") (pin "2") (pinfunction "2_2") (pintype "passive"))
      (node (ref "R46") (pin "2") (pinfunction "2_2") (pintype "passive"))
      (node (ref "R47") (pin "2") (pinfunction "2_2") (pintype "passive"))
      (node (ref "R63") (pin "1") (pinfunction "1_1") (pintype "passive"))
      (node (ref "R64") (pin "1") (pinfunction "1_1") (pintype "passive"))
      (node (ref "R65") (pin "1") (pinfunction "1_1") (pintype "passive"))
      (node (ref "U3") (pin "13") (pinfunction "VDD_13") (pintype "power_in"))
      (node (ref "U4") (pin "19") (pinfunction "VCCB_19") (pintype "bidirectional"))
      (node (ref "U5") (pin "14") (pinfunction "VCC_14") (pintype "power_in"))
      (node (ref "U6") (pin "14") (pinfunction "VCC_14") (pintype "power_in"))
    )
    (net (code "3") (name "12V") (class "Default")
      (node (ref "C16") (pin "2") (pinfunction "P$2_2") (pintype "passive"))
      (node (ref "C7") (pin "+") (pinfunction "+_+") (pintype "passive"))
      (node (ref "IC2") (pin "1") (pinfunction "IN_1") (pintype "input"))
      (node (ref "IC5") (pin "3") (pinfunction "VIN_3") (pintype "input"))
      (node (ref "J1") (pin "A4") (pinfunction "A_A4") (pintype "bidirectional"))
      (node (ref "PTC2") (pin "P$1") (pinfunction "1_P$1") (pintype "passive"))
    )
    (net (code "4") (name "ADC_CS") (class "Default")
      (node (ref "U$1") (pin "P$12") (pinfunction "PE9_P$12") (pintype "bidirectional"))
      (node (ref "U8") (pin "8") (pinfunction "*CS/SHDN_8") (pintype "input"))
    )
    (net (code "5") (name "AUX1") (class "Default")
      (node (ref "J1") (pin "D1") (pinfunction "D_D1") (pintype "bidirectional"))
    )
    (net (code "6") (name "AUX2") (class "Default")
      (node (ref "J1") (pin "E1") (pinfunction "E_E1") (pintype "bidirectional"))
      (node (ref "S2") (pin "2") (pinfunction "P_2") (pintype "passive"))
    )
    (net (code "7") (name "AUX2I") (class "Default")
      (node (ref "R60") (pin "2") (pinfunction "2_2") (pintype "passive"))
      (node (ref "S2") (pin "1") (pinfunction "O_1") (pintype "passive"))
      (node (ref "U$1") (pin "P$17") (pinfunction "PE14_P$17") (pintype "bidirectional"))
    )
    (net (code "8") (name "AUX3") (class "Default")
      (node (ref "J1") (pin "E2") (pinfunction "E_E2") (pintype "bidirectional"))
      (node (ref "S3") (pin "2") (pinfunction "P_2") (pintype "passive"))
    )
    (net (code "9") (name "AUX3I") (class "Default")
      (node (ref "R61") (pin "2") (pinfunction "2_2") (pintype "passive"))
      (node (ref "S3") (pin "1") (pinfunction "O_1") (pintype "passive"))
      (node (ref "U$1") (pin "P$18") (pinfunction "PE15_P$18") (pintype "bidirectional"))
    )
    (net (code "10") (name "AUX4") (class "Default")
      (node (ref "J1") (pin "E3") (pinfunction "E_E3") (pintype "bidirectional"))
      (node (ref "S4") (pin "2") (pinfunction "P_2") (pintype "passive"))
    )
    (net (code "11") (name "AUX4I") (class "Default")
      (node (ref "R62") (pin "2") (pinfunction "2_2") (pintype "passive"))
      (node (ref "S4") (pin "1") (pinfunction "O_1") (pintype "passive"))
      (node (ref "U$1") (pin "P$21") (pinfunction "PB10_P$21") (pintype "bidirectional"))
    )
    (net (code "12") (name "AUX5") (class "Default")
      (node (ref "J1") (pin "E4") (pinfunction "E_E4") (pintype "bidirectional"))
      (node (ref "U$1") (pin "P$22") (pinfunction "PB11_P$22") (pintype "bidirectional"))
    )
    (net (code "13") (name "AUX6") (class "Default")
      (node (ref "J2") (pin "E1") (pinfunction "E_E1") (pintype "bidirectional"))
      (node (ref "U$1") (pin "P$65") (pinfunction "PE4_P$65") (pintype "bidirectional"))
    )
    (net (code "14") (name "AUX7") (class "Default")
      (node (ref "J2") (pin "E3") (pinfunction "E_E3") (pintype "bidirectional"))
      (node (ref "U$1") (pin "P$66") (pinfunction "PE5_P$66") (pintype "bidirectional"))
    )
    (net (code "15") (name "BITE") (class "Default")
      (node (ref "J1") (pin "A1") (pinfunction "A_A1") (pintype "bidirectional"))
      (node (ref "Q11") (pin "3") (pinfunction "C_3") (pintype "passive"))
      (node (ref "R65") (pin "2") (pinfunction "2_2") (pintype "passive"))
    )
    (net (code "16") (name "BITEL") (class "Default")
      (node (ref "Q11") (pin "2") (pinfunction "E_2") (pintype "passive"))
      (node (ref "U$1") (pin "P$13") (pinfunction "PE10_P$13") (pintype "bidirectional"))
    )
    (net (code "17") (name "BRAKE-POT") (class "Default")
      (node (ref "J1") (pin "C3") (pinfunction "C_C3") (pintype "bidirectional"))
      (node (ref "U$57") (pin "3") (pinfunction "VIN+_3") (pintype "input"))
    )
    (net (code "18") (name "BRAKE-POTB") (class "Default")
      (node (ref "U$1") (pin "P$8") (pinfunction "PB0_P$8") (pintype "bidirectional"))
      (node (ref "U$57") (pin "1") (pinfunction "VOUT_1") (pintype "output"))
      (node (ref "U$57") (pin "4") (pinfunction "VIN-_4") (pintype "input"))
    )
    (net (code "19") (name "BRAKEP") (class "Default")
      (node (ref "J2") (pin "F4") (pinfunction "F_F4") (pintype "bidirectional"))
      (node (ref "R19") (pin "2") (pinfunction "2_2") (pintype "passive"))
      (node (ref "U$39") (pin "3") (pinfunction "VIN+_3") (pintype "input"))
    )
    (net (code "20") (name "BRAKEP2") (class "Default")
      (node (ref "J2") (pin "F2") (pinfunction "F_F2") (pintype "bidirectional"))
      (node (ref "R15") (pin "2") (pinfunction "2_2") (pintype "passive"))
      (node (ref "U$43") (pin "3") (pinfunction "VIN+_3") (pintype "input"))
    )
    (net (code "21") (name "BRAKEP2B") (class "Default")
      (node (ref "U$1") (pin "P$76") (pinfunction "PA1_P$76") (pintype "bidirectional"))
      (node (ref "U$43") (pin "1") (pinfunction "VOUT_1") (pintype "output"))
      (node (ref "U$43") (pin "4") (pinfunction "VIN-_4") (pintype "input"))
    )
    (net (code "22") (name "BRAKEPB") (class "Default")
      (node (ref "U$1") (pin "P$75") (pinfunction "PA0_P$75") (pintype "bidirectional"))
      (node (ref "U$39") (pin "1") (pinfunction "VOUT_1") (pintype "output"))
      (node (ref "U$39") (pin "4") (pinfunction "VIN-_4") (pintype "input"))
    )
    (net (code "23") (name "CANH") (class "Default")
      (node (ref "J2") (pin "D2") (pinfunction "D_D2") (pintype "bidirectional"))
      (node (ref "R7") (pin "1") (pinfunction "1_1") (pintype "passive"))
      (node (ref "U1") (pin "6") (pinfunction "CANL_6") (pintype "input"))
    )
    (net (code "24") (name "CANL") (class "Default")
      (node (ref "J2") (pin "D1") (pinfunction "D_D1") (pintype "bidirectional"))
      (node (ref "R3") (pin "1") (pinfunction "1_1") (pintype "passive"))
      (node (ref "U1") (pin "7") (pinfunction "CANH_7") (pintype "input"))
    )
    (net (code "25") (name "CAN_RX") (class "Default")
      (node (ref "U$1") (pin "P$55") (pinfunction "PB5_P$55") (pintype "bidirectional"))
      (node (ref "U1") (pin "4") (pinfunction "RXD_4") (pintype "output"))
    )
    (net (code "26") (name "CAN_TX") (class "Default")
      (node (ref "U$1") (pin "P$56") (pinfunction "PB6_P$56") (pintype "bidirectional"))
      (node (ref "U1") (pin "1") (pinfunction "TXD_1") (pintype "input"))
    )
    (net (code "27") (name "CLUTCH-POT") (class "Default")
      (node (ref "J1") (pin "C4") (pinfunction "C_C4") (pintype "bidirectional"))
      (node (ref "U$59") (pin "3") (pinfunction "VIN+_3") (pintype "input"))
    )
    (net (code "28") (name "CLUTCH-POTB") (class "Default")
      (node (ref "U$1") (pin "P$9") (pinfunction "PB1_P$9") (pintype "bidirectional"))
      (node (ref "U$59") (pin "1") (pinfunction "VOUT_1") (pintype "output"))
      (node (ref "U$59") (pin "4") (pinfunction "VIN-_4") (pintype "input"))
    )
    (net (code "29") (name "COMRX") (class "Default")
      (node (ref "U$1") (pin "P$52") (pinfunction "PD6_P$52") (pintype "bidirectional"))
      (node (ref "U2") (pin "9") (pinfunction "R2OUT_9") (pintype "output"))
    )
    (net (code "30") (name "COMTX") (class "Default")
      (node (ref "U$1") (pin "P$51") (pinfunction "PD5_P$51") (pintype "bidirectional"))
      (node (ref "U2") (pin "10") (pinfunction "T2IN_10") (pintype "input"))
    )
    (net (code "31") (name "DACCLR") (class "Default")
      (node (ref "U$1") (pin "P$23") (pinfunction "PB12_P$23") (pintype "bidirectional"))
      (node (ref "U3") (pin "3") (pinfunction "~{CLR}_3") (pintype "input"))
    )
    (net (code "32") (name "DACCS") (class "Default")
      (node (ref "U$1") (pin "P$28") (pinfunction "PD9_P$28") (pintype "bidirectional"))
      (node (ref "U3") (pin "5") (pinfunction "~{CS}_5") (pintype "input"))
    )
    (net (code "33") (name "ECU1") (class "Default")
      (node (ref "J2") (pin "C4") (pinfunction "C_C4") (pintype "bidirectional"))
      (node (ref "Q1") (pin "3") (pinfunction "C_3") (pintype "passive"))
      (node (ref "R64") (pin "2") (pinfunction "2_2") (pintype "passive"))
    )
    (net (code "34") (name "ECU1L") (class "Default")
      (node (ref "Q1") (pin "2") (pinfunction "E_2") (pintype "passive"))
      (node (ref "U$1") (pin "P$67") (pinfunction "PE6_P$67") (pintype "bidirectional"))
    )
    (net (code "35") (name "ECU2") (class "Default")
      (node (ref "J2") (pin "D4") (pinfunction "D_D4") (pintype "bidirectional"))
      (node (ref "Q2") (pin "3") (pinfunction "C_3") (pintype "passive"))
      (node (ref "R63") (pin "2") (pinfunction "2_2") (pintype "passive"))
    )
    (net (code "36") (name "ECU2L") (class "Default")
      (node (ref "Q2") (pin "2") (pinfunction "E_2") (pintype "passive"))
      (node (ref "U$1") (pin "P$68") (pinfunction "PC13_P$68") (pintype "bidirectional"))
    )
    (net (code "37") (name "ENCODER1") (class "Default")
      (node (ref "C32") (pin "1") (pinfunction "P$1_1") (pintype "passive"))
      (node (ref "J1") (pin "G2") (pinfunction "G_G2") (pintype "bidirectional"))
      (node (ref "R35") (pin "2") (pinfunction "2_2") (pintype "passive"))
      (node (ref "U$1") (pin "P$14") (pinfunction "PE11_P$14") (pintype "bidirectional"))
    )
    (net (code "38") (name "ENCODER2") (class "Default")
      (node (ref "C33") (pin "1") (pinfunction "P$1_1") (pintype "passive"))
      (node (ref "J1") (pin "G3") (pinfunction "G_G3") (pintype "bidirectional"))
      (node (ref "R36") (pin "2") (pinfunction "2_2") (pintype "passive"))
      (node (ref "U$1") (pin "P$15") (pinfunction "PE12_P$15") (pintype "bidirectional"))
    )
    (net (code "39") (name "FUELTEMP") (class "Default")
      (node (ref "J1") (pin "C2") (pinfunction "C_C2") (pintype "bidirectional"))
      (node (ref "R22") (pin "2") (pinfunction "2_2") (pintype "passive"))
      (node (ref "U$55") (pin "3") (pinfunction "VIN+_3") (pintype "input"))
    )
    (net (code "40") (name "FUELTEMPB") (class "Default")
      (node (ref "U$1") (pin "P$7") (pinfunction "PC5_P$7") (pintype "bidirectional"))
      (node (ref "U$55") (pin "1") (pinfunction "VOUT_1") (pintype "output"))
      (node (ref "U$55") (pin "4") (pinfunction "VIN-_4") (pintype "input"))
    )
    (net (code "41") (name "GEARPOSAN") (class "Default")
      (node (ref "J2") (pin "H3") (pinfunction "H_H3") (pintype "bidirectional"))
      (node (ref "U$49") (pin "3") (pinfunction "VIN+_3") (pintype "input"))
    )
    (net (code "42") (name "GEARPOSANB") (class "Default")
      (node (ref "U$1") (pin "P$71") (pinfunction "PC0_P$71") (pintype "bidirectional"))
      (node (ref "U$49") (pin "1") (pinfunction "VOUT_1") (pintype "output"))
      (node (ref "U$49") (pin "4") (pinfunction "VIN-_4") (pintype "input"))
    )
    (net (code "43") (name "GND") (class "Default")
      (node (ref "C1") (pin "1") (pinfunction "P$1_1") (pintype "passive"))
      (node (ref "C10") (pin "1") (pinfunction "P$1_1") (pintype "passive"))
      (node (ref "C11") (pin "2") (pinfunction "P$2_2") (pintype "passive"))
      (node (ref "C12") (pin "1") (pinfunction "P$1_1") (pintype "passive"))
      (node (ref "C13") (pin "2") (pinfunction "P$2_2") (pintype "passive"))
      (node (ref "C15") (pin "-") (pinfunction "-_-") (pintype "passive"))
      (node (ref "C16") (pin "1") (pinfunction "P$1_1") (pintype "passive"))
      (node (ref "C17") (pin "1") (pinfunction "P$1_1") (pintype "passive"))
      (node (ref "C18") (pin "1") (pinfunction "P$1_1") (pintype "passive"))
      (node (ref "C19") (pin "1") (pinfunction "P$1_1") (pintype "passive"))
      (node (ref "C2") (pin "-") (pinfunction "-_-") (pintype "passive"))
      (node (ref "C20") (pin "1") (pinfunction "P$1_1") (pintype "passive"))
      (node (ref "C21") (pin "1") (pinfunction "P$1_1") (pintype "passive"))
      (node (ref "C22") (pin "1") (pinfunction "P$1_1") (pintype "passive"))
      (node (ref "C23") (pin "1") (pinfunction "P$1_1") (pintype "passive"))
      (node (ref "C24") (pin "1") (pinfunction "P$1_1") (pintype "passive"))
      (node (ref "C25") (pin "1") (pinfunction "P$1_1") (pintype "passive"))
      (node (ref "C26") (pin "1") (pinfunction "P$1_1") (pintype "passive"))
      (node (ref "C27") (pin "1") (pinfunction "P$1_1") (pintype "passive"))
      (node (ref "C28") (pin "1") (pinfunction "P$1_1") (pintype "passive"))
      (node (ref "C29") (pin "1") (pinfunction "P$1_1") (pintype "passive"))
      (node (ref "C3") (pin "2") (pinfunction "P$2_2") (pintype "passive"))
      (node (ref "C30") (pin "1") (pinfunction "P$1_1") (pintype "passive"))
      (node (ref "C31") (pin "1") (pinfunction "P$1_1") (pintype "passive"))
      (node (ref "C32") (pin "2") (pinfunction "P$2_2") (pintype "passive"))
      (node (ref "C33") (pin "2") (pinfunction "P$2_2") (pintype "passive"))
      (node (ref "C38") (pin "2") (pinfunction "P$2_2") (pintype "passive"))
      (node (ref "C39") (pin "2") (pinfunction "P$2_2") (pintype "passive"))
      (node (ref "C4") (pin "2") (pinfunction "P$2_2") (pintype "passive"))
      (node (ref "C40") (pin "2") (pinfunction "P$2_2") (pintype "passive"))
      (node (ref "C5") (pin "2") (pinfunction "P$2_2") (pintype "passive"))
      (node (ref "C6") (pin "1") (pinfunction "P$1_1") (pintype "passive"))
      (node (ref "C7") (pin "-") (pinfunction "-_-") (pintype "passive"))
      (node (ref "D2") (pin "A") (pinfunction "A_A") (pintype "passive"))
      (node (ref "IC2") (pin "3") (pinfunction "GND_3") (pintype "power_in"))
      (node (ref "IC2") (pin "5") (pinfunction "EN_5") (pintype "input"))
      (node (ref "IC2") (pin "6") (pinfunction "GND_6") (pintype "power_in"))
      (node (ref "IC5") (pin "1") (pinfunction "GND_1") (pintype "power_in"))
      (node (ref "J1") (pin "B1") (pinfunction "B_B1") (pintype "bidirectional"))
      (node (ref "J1") (pin "B2") (pinfunction "B_B2") (pintype "bidirectional"))
      (node (ref "J1") (pin "B3") (pinfunction "B_B3") (pintype "bidirectional"))
      (node (ref "J1") (pin "B4") (pinfunction "B_B4") (pintype "bidirectional"))
      (node (ref "J1") (pin "D2") (pinfunction "D_D2") (pintype "bidirectional"))
      (node (ref "J1") (pin "F1") (pinfunction "F_F1") (pintype "bidirectional"))
      (node (ref "J1") (pin "F2") (pinfunction "F_F2") (pintype "bidirectional"))
      (node (ref "J1") (pin "F3") (pinfunction "F_F3") (pintype "bidirectional"))
      (node (ref "J1") (pin "F4") (pinfunction "F_F4") (pintype "bidirectional"))
      (node (ref "J1") (pin "G1") (pinfunction "G_G1") (pintype "bidirectional"))
      (node (ref "J1") (pin "H4") (pinfunction "H_H4") (pintype "bidirectional"))
      (node (ref "J1") (pin "J1") (pinfunction "J_J1") (pintype "bidirectional"))
      (node (ref "J1") (pin "M4") (pinfunction "M_M4") (pintype "bidirectional"))
      (node (ref "J2") (pin "C3") (pinfunction "C_C3") (pintype "bidirectional"))
      (node (ref "J2") (pin "D3") (pinfunction "D_D3") (pintype "bidirectional"))
      (node (ref "J2") (pin "E2") (pinfunction "E_E2") (pintype "bidirectional"))
      (node (ref "J2") (pin "E4") (pinfunction "E_E4") (pintype "bidirectional"))
      (node (ref "J2") (pin "G1") (pinfunction "G_G1") (pintype "bidirectional"))
      (node (ref "J2") (pin "G2") (pinfunction "G_G2") (pintype "bidirectional"))
      (node (ref "J2") (pin "G3") (pinfunction "G_G3") (pintype "bidirectional"))
      (node (ref "J2") (pin "G4") (pinfunction "G_G4") (pintype "bidirectional"))
      (node (ref "J2") (pin "H2") (pinfunction "H_H2") (pintype "bidirectional"))
      (node (ref "J2") (pin "J2") (pinfunction "J_J2") (pintype "bidirectional"))
      (node (ref "J2") (pin "M1") (pinfunction "M_M1") (pintype "bidirectional"))
      (node (ref "J2") (pin "M2") (pinfunction "M_M2") (pintype "bidirectional"))
      (node (ref "J2") (pin "M3") (pinfunction "M_M3") (pintype "bidirectional"))
      (node (ref "J2") (pin "M4") (pinfunction "M_M4") (pintype "bidirectional"))
      (node (ref "OK1") (pin "2") (pinfunction "C_2") (pintype "passive"))
      (node (ref "OK2") (pin "2") (pinfunction "C_2") (pintype "passive"))
      (node (ref "OK3") (pin "2") (pinfunction "C_2") (pintype "passive"))
      (node (ref "OK4") (pin "2") (pinfunction "C_2") (pintype "passive"))
      (node (ref "OK5") (pin "2") (pinfunction "C_2") (pintype "passive"))
      (node (ref "OK6") (pin "2") (pinfunction "C_2") (pintype "passive"))
      (node (ref "Q3") (pin "2") (pinfunction "E_2") (pintype "passive"))
      (node (ref "R1") (pin "1") (pinfunction "1_1") (pintype "passive"))
      (node (ref "R31") (pin "1") (pinfunction "1_1") (pintype "passive"))
      (node (ref "R5") (pin "1") (pinfunction "1_1") (pintype "passive"))
      (node (ref "R55") (pin "1") (pinfunction "1_1") (pintype "passive"))
      (node (ref "R57") (pin "1") (pinfunction "1_1") (pintype "passive"))
      (node (ref "R59") (pin "1") (pinfunction "1_1") (pintype "passive"))
      (node (ref "R8") (pin "1") (pinfunction "1_1") (pintype "passive"))
      (node (ref "U$1") (pin "P$19") (pinfunction "GND1_P$19") (pintype "bidirectional"))
      (node (ref "U$1") (pin "P$20") (pinfunction "GND2_P$20") (pintype "bidirectional"))
      (node (ref "U$1") (pin "P$41") (pinfunction "GND3_P$41") (pintype "bidirectional"))
      (node (ref "U$1") (pin "P$42") (pinfunction "GND4_P$42") (pintype "bidirectional"))
      (node (ref "U$1") (pin "P$62") (pinfunction "GND5_P$62") (pintype "bidirectional"))
      (node (ref "U$1") (pin "P$69") (pinfunction "GND6_P$69") (pintype "bidirectional"))
      (node (ref "U$1") (pin "P$70") (pinfunction "GND7_P$70") (pintype "bidirectional"))
      (node (ref "U$1") (pin "P$78") (pinfunction "GND8_P$78") (pintype "bidirectional"))
      (node (ref "U$19") (pin "2") (pinfunction "VSS_2") (pintype "passive"))
      (node (ref "U$24") (pin "2") (pinfunction "VSS_2") (pintype "passive"))
      (node (ref "U$30") (pin "2") (pinfunction "VSS_2") (pintype "passive"))
      (node (ref "U$33") (pin "2") (pinfunction "VSS_2") (pintype "passive"))
      (node (ref "U$34") (pin "2") (pinfunction "VSS_2") (pintype "passive"))
      (node (ref "U$37") (pin "2") (pinfunction "VSS_2") (pintype "passive"))
      (node (ref "U$39") (pin "2") (pinfunction "VSS_2") (pintype "passive"))
      (node (ref "U$40") (pin "2") (pinfunction "VSS_2") (pintype "passive"))
      (node (ref "U$43") (pin "2") (pinfunction "VSS_2") (pintype "passive"))
      (node (ref "U$45") (pin "2") (pinfunction "VSS_2") (pintype "passive"))
      (node (ref "U$47") (pin "2") (pinfunction "VSS_2") (pintype "passive"))
      (node (ref "U$49") (pin "2") (pinfunction "VSS_2") (pintype "passive"))
      (node (ref "U$55") (pin "2") (pinfunction "VSS_2") (pintype "passive"))
      (node (ref "U$57") (pin "2") (pinfunction "VSS_2") (pintype "passive"))
      (node (ref "U$59") (pin "2") (pinfunction "VSS_2") (pintype "passive"))
      (node (ref "U1") (pin "2") (pinfunction "GND_2") (pintype "passive"))
      (node (ref "U1") (pin "8") (pinfunction "RS_8") (pintype "input"))
      (node (ref "U2") (pin "15") (pinfunction "GND_15") (pintype "passive"))
      (node (ref "U3") (pin "1") (pinfunction "BIPOFF_1") (pintype "passive"))
      (node (ref "U3") (pin "11") (pinfunction "VSS_11") (pintype "power_in"))
      (node (ref "U3") (pin "7") (pinfunction "DGND_7") (pintype "passive"))
      (node (ref "U3") (pin "8") (pinfunction "AGND_8") (pintype "passive"))
      (node (ref "U4") (pin "11") (pinfunction "GND_11") (pintype "bidirectional"))
      (node (ref "U5") (pin "1") (pinfunction "IN_THRS1_1") (pintype "input"))
      (node (ref "U5") (pin "11") (pinfunction "GND_11") (pintype "passive"))
      (node (ref "U5") (pin "13") (pinfunction "OUT1_13") (pintype "output"))
      (node (ref "U5") (pin "3") (pinfunction "BIAS_3") (pintype "input"))
      (node (ref "U5") (pin "6") (pinfunction "BIAS2_6") (pintype "input"))
      (node (ref "U5") (pin "8") (pinfunction "INT_THRS2_8") (pintype "input"))
      (node (ref "U6") (pin "1") (pinfunction "IN_THRS1_1") (pintype "input"))
      (node (ref "U6") (pin "11") (pinfunction "GND_11") (pintype "passive"))
      (node (ref "U6") (pin "13") (pinfunction "OUT1_13") (pintype "output"))
      (node (ref "U6") (pin "3") (pinfunction "BIAS_3") (pintype "input"))
      (node (ref "U6") (pin "6") (pinfunction "BIAS2_6") (pintype "input"))
      (node (ref "U6") (pin "8") (pinfunction "INT_THRS2_8") (pintype "input"))
      (node (ref "U7") (pin "8") (pinfunction "VSS_8") (pintype "power_in"))
      (node (ref "U8") (pin "12") (pinfunction "AGND_12") (pintype "passive"))
      (node (ref "U8") (pin "7") (pinfunction "DGND_7") (pintype "passive"))
    )
    (net (code "44") (name "GND-RELAY") (class "Default")
      (node (ref "D1") (pin "A") (pinfunction "A_A") (pintype "passive"))
      (node (ref "D3") (pin "A") (pinfunction "A_A") (pintype "passive"))
      (node (ref "D4") (pin "A") (pinfunction "A_A") (pintype "passive"))
      (node (ref "D5") (pin "A") (pinfunction "A_A") (pintype "passive"))
      (node (ref "D6") (pin "A") (pinfunction "A_A") (pintype "passive"))
      (node (ref "D7") (pin "A") (pinfunction "A_A") (pintype "passive"))
      (node (ref "J1") (pin "K1") (pinfunction "K_K1") (pintype "bidirectional"))
      (node (ref "OK1") (pin "4") (pinfunction "EMI_4") (pintype "passive"))
      (node (ref "OK2") (pin "4") (pinfunction "EMI_4") (pintype "passive"))
      (node (ref "OK3") (pin "4") (pinfunction "EMI_4") (pintype "passive"))
      (node (ref "OK4") (pin "4") (pinfunction "EMI_4") (pintype "passive"))
      (node (ref "OK5") (pin "4") (pinfunction "EMI_4") (pintype "passive"))
      (node (ref "OK6") (pin "4") (pinfunction "EMI_4") (pintype "passive"))
      (node (ref "R10") (pin "2") (pinfunction "2_2") (pintype "passive"))
      (node (ref "R16") (pin "2") (pinfunction "2_2") (pintype "passive"))
      (node (ref "R20") (pin "2") (pinfunction "2_2") (pintype "passive"))
      (node (ref "R23") (pin "2") (pinfunction "2_2") (pintype "passive"))
      (node (ref "R28") (pin "2") (pinfunction "2_2") (pintype "passive"))
      (node (ref "R9") (pin "2") (pinfunction "2_2") (pintype "passive"))
    )
    (net (code "45") (name "GSENS") (class "Default")
      (node (ref "J1") (pin "A2") (pinfunction "A_A2") (pintype "bidirectional"))
      (node (ref "R4") (pin "2") (pinfunction "2_2") (pintype "passive"))
    )
    (net (code "46") (name "GSENSO") (class "Default")
      (node (ref "R33") (pin "1") (pinfunction "1_1") (pintype "passive"))
      (node (ref "U$1") (pin "P$5") (pinfunction "PA7_P$5") (pintype "bidirectional"))
      (node (ref "U$24") (pin "1") (pinfunction "VOUT_1") (pintype "output"))
      (node (ref "U$24") (pin "4") (pinfunction "VIN-_4") (pintype "input"))
    )
    (net (code "47") (name "HB1-DIR") (class "Default")
      (node (ref "U$1") (pin "P$29") (pinfunction "PD10_P$29") (pintype "bidirectional"))
      (node (ref "U4") (pin "6") (pinfunction "A5_6") (pintype "bidirectional"))
    )
    (net (code "48") (name "HB1-DIR-IN") (class "Default")
      (node (ref "J1") (pin "J4") (pinfunction "J_J4") (pintype "bidirectional"))
      (node (ref "U4") (pin "15") (pinfunction "B5_15") (pintype "bidirectional"))
    )
    (net (code "49") (name "HB1-EN") (class "Default")
      (node (ref "U$1") (pin "P$30") (pinfunction "PD11_P$30") (pintype "bidirectional"))
      (node (ref "U4") (pin "7") (pinfunction "A6_7") (pintype "bidirectional"))
    )
    (net (code "50") (name "HB1-EN-IN") (class "Default")
      (node (ref "J1") (pin "H1") (pinfunction "H_H1") (pintype "bidirectional"))
      (node (ref "U4") (pin "14") (pinfunction "B6_14") (pintype "bidirectional"))
    )
    (net (code "51") (name "HB1-PWM") (class "Default")
      (node (ref "U$1") (pin "P$32") (pinfunction "PD13_P$32") (pintype "bidirectional"))
      (node (ref "U4") (pin "5") (pinfunction "A4_5") (pintype "bidirectional"))
    )
    (net (code "52") (name "HB1-PWM-IN") (class "Default")
      (node (ref "J1") (pin "J3") (pinfunction "J_J3") (pintype "bidirectional"))
      (node (ref "U4") (pin "16") (pinfunction "B4_16") (pintype "bidirectional"))
    )
    (net (code "53") (name "HB2-DIR") (class "Default")
      (node (ref "U$1") (pin "P$34") (pinfunction "PD15_P$34") (pintype "bidirectional"))
      (node (ref "U4") (pin "3") (pinfunction "A2_3") (pintype "bidirectional"))
    )
    (net (code "54") (name "HB2-DIR-IN") (class "Default")
      (node (ref "J1") (pin "K4") (pinfunction "K_K4") (pintype "bidirectional"))
      (node (ref "U4") (pin "18") (pinfunction "B2_18") (pintype "bidirectional"))
    )
    (net (code "55") (name "HB2-EN") (class "Default")
      (node (ref "U$1") (pin "P$33") (pinfunction "PD14_P$33") (pintype "bidirectional"))
      (node (ref "U4") (pin "1") (pinfunction "A1_1") (pintype "bidirectional"))
    )
    (net (code "56") (name "HB2-EN-IN") (class "Default")
      (node (ref "J1") (pin "K3") (pinfunction "K_K3") (pintype "bidirectional"))
      (node (ref "U4") (pin "20") (pinfunction "B1_20") (pintype "bidirectional"))
    )
    (net (code "57") (name "HB2-PWM") (class "Default")
      (node (ref "U$1") (pin "P$31") (pinfunction "PD12_P$31") (pintype "bidirectional"))
      (node (ref "U4") (pin "4") (pinfunction "A3_4") (pintype "bidirectional"))
    )
    (net (code "58") (name "HB2-PWM-IN") (class "Default")
      (node (ref "J1") (pin "J2") (pinfunction "J_J2") (pintype "bidirectional"))
      (node (ref "U4") (pin "17") (pinfunction "B3_17") (pintype "bidirectional"))
    )
    (net (code "59") (name "IGNCUT") (class "Default")
      (node (ref "R17") (pin "2") (pinfunction "2_2") (pintype "passive"))
      (node (ref "U$1") (pin "P$10") (pinfunction "PE7_P$10") (pintype "bidirectional"))
    )
    (net (code "60") (name "IGNCUTO") (class "Default")
      (node (ref "J2") (pin "H1") (pinfunction "H_H1") (pintype "bidirectional"))
      (node (ref "Q3") (pin "3") (pinfunction "C_3") (pintype "passive"))
    )
    (net (code "61") (name "MISO") (class "Default")
      (node (ref "U$1") (pin "P$25") (pinfunction "PB14_P$25") (pintype "bidirectional"))
      (node (ref "U3") (pin "6") (pinfunction "DOUT_6") (pintype "output"))
      (node (ref "U8") (pin "10") (pinfunction "DOUT_10") (pintype "output"))
    )
    (net (code "62") (name "MOSI") (class "Default")
      (node (ref "U$1") (pin "P$26") (pinfunction "PB15_P$26") (pintype "bidirectional"))
      (node (ref "U3") (pin "2") (pinfunction "DIN_2") (pintype "input"))
      (node (ref "U8") (pin "9") (pinfunction "DIN_9") (pintype "input"))
    )
    (net (code "63") (name "NEUTRAL") (class "Default")
      (node (ref "J2") (pin "J1") (pinfunction "J_J1") (pintype "bidirectional"))
      (node (ref "R37") (pin "2") (pinfunction "2_2") (pintype "passive"))
      (node (ref "U$1") (pin "P$11") (pinfunction "PE8_P$11") (pintype "bidirectional"))
    )
    (net (code "64") (name "Net-(C5-P$1)") (class "Default")
      (node (ref "C5") (pin "1") (pinfunction "P$1_1") (pintype "passive"))
      (node (ref "R3") (pin "2") (pinfunction "2_2") (pintype "passive"))
      (node (ref "R7") (pin "2") (pinfunction "2_2") (pintype "passive"))
      (node (ref "U1") (pin "5") (pinfunction "SPLIT_5") (pintype "output"))
    )
    (net (code "65") (name "Net-(C8-P$1)") (class "Default")
      (node (ref "C8") (pin "1") (pinfunction "P$1_1") (pintype "passive"))
      (node (ref "U2") (pin "1") (pinfunction "C1+_1") (pintype "input"))
    )
    (net (code "66") (name "Net-(C8-P$2)") (class "Default")
      (node (ref "C8") (pin "2") (pinfunction "P$2_2") (pintype "passive"))
      (node (ref "U2") (pin "3") (pinfunction "C1-_3") (pintype "input"))
    )
    (net (code "67") (name "Net-(C9-P$1)") (class "Default")
      (node (ref "C9") (pin "1") (pinfunction "P$1_1") (pintype "passive"))
      (node (ref "U2") (pin "4") (pinfunction "C2+_4") (pintype "input"))
    )
    (net (code "68") (name "Net-(C9-P$2)") (class "Default")
      (node (ref "C9") (pin "2") (pinfunction "P$2_2") (pintype "passive"))
      (node (ref "U2") (pin "5") (pinfunction "C2-_5") (pintype "input"))
    )
    (net (code "69") (name "Net-(C11-P$1)") (class "Default")
      (node (ref "C11") (pin "1") (pinfunction "P$1_1") (pintype "passive"))
      (node (ref "U2") (pin "2") (pinfunction "V+_2") (pintype "power_in"))
    )
    (net (code "70") (name "Net-(C12-P$2)") (class "Default")
      (node (ref "C12") (pin "2") (pinfunction "P$2_2") (pintype "passive"))
      (node (ref "U2") (pin "6") (pinfunction "V-_6") (pintype "power_in"))
    )
    (net (code "71") (name "Net-(C34-P$1)") (class "Default")
      (node (ref "C34") (pin "1") (pinfunction "P$1_1") (pintype "passive"))
      (node (ref "R27") (pin "2") (pinfunction "2_2") (pintype "passive"))
      (node (ref "R40") (pin "2") (pinfunction "2_2") (pintype "passive"))
      (node (ref "U5") (pin "16") (pinfunction "IN1+_16") (pintype "input"))
    )
    (net (code "72") (name "Net-(C34-P$2)") (class "Default")
      (node (ref "C34") (pin "2") (pinfunction "P$2_2") (pintype "passive"))
      (node (ref "R39") (pin "2") (pinfunction "2_2") (pintype "passive"))
      (node (ref "R40") (pin "1") (pinfunction "1_1") (pintype "passive"))
      (node (ref "U5") (pin "15") (pinfunction "IN1-_15") (pintype "input"))
    )
    (net (code "73") (name "Net-(C35-P$1)") (class "Default")
      (node (ref "C35") (pin "1") (pinfunction "P$1_1") (pintype "passive"))
      (node (ref "R41") (pin "2") (pinfunction "2_2") (pintype "passive"))
      (node (ref "R43") (pin "2") (pinfunction "2_2") (pintype "passive"))
      (node (ref "U5") (pin "9") (pinfunction "IN2+_9") (pintype "input"))
    )
    (net (code "74") (name "Net-(C35-P$2)") (class "Default")
      (node (ref "C35") (pin "2") (pinfunction "P$2_2") (pintype "passive"))
      (node (ref "R42") (pin "2") (pinfunction "2_2") (pintype "passive"))
      (node (ref "R43") (pin "1") (pinfunction "1_1") (pintype "passive"))
      (node (ref "U5") (pin "10") (pinfunction "IN2-_10") (pintype "input"))
    )
    (net (code "75") (name "Net-(C36-P$1)") (class "Default")
      (node (ref "C36") (pin "1") (pinfunction "P$1_1") (pintype "passive"))
      (node (ref "R48") (pin "2") (pinfunction "2_2") (pintype "passive"))
      (node (ref "R50") (pin "2") (pinfunction "2_2") (pintype "passive"))
      (node (ref "U6") (pin "16") (pinfunction "IN1+_16") (pintype "input"))
    )
    (net (code "76") (name "Net-(C36-P$2)") (class "Default")
      (node (ref "C36") (pin "2") (pinfunction "P$2_2") (pintype "passive"))
      (node (ref "R49") (pin "2") (pinfunction "2_2") (pintype "passive"))
      (node (ref "R50") (pin "1") (pinfunction "1_1") (pintype "passive"))
      (node (ref "U6") (pin "15") (pinfunction "IN1-_15") (pintype "input"))
    )
    (net (code "77") (name "Net-(C37-P$1)") (class "Default")
      (node (ref "C37") (pin "1") (pinfunction "P$1_1") (pintype "passive"))
      (node (ref "R51") (pin "2") (pinfunction "2_2") (pintype "passive"))
      (node (ref "R53") (pin "2") (pinfunction "2_2") (pintype "passive"))
      (node (ref "U6") (pin "9") (pinfunction "IN2+_9") (pintype "input"))
    )
    (net (code "78") (name "Net-(C37-P$2)") (class "Default")
      (node (ref "C37") (pin "2") (pinfunction "P$2_2") (pintype "passive"))
      (node (ref "R52") (pin "2") (pinfunction "2_2") (pintype "passive"))
      (node (ref "R53") (pin "1") (pinfunction "1_1") (pintype "passive"))
      (node (ref "U6") (pin "10") (pinfunction "IN2-_10") (pintype "input"))
    )
    (net (code "79") (name "Net-(IC2-FB)") (class "Default")
      (node (ref "IC2") (pin "4") (pinfunction "FB_4") (pintype "input"))
      (node (ref "R1") (pin "2") (pinfunction "2_2") (pintype "passive"))
      (node (ref "R2") (pin "2") (pinfunction "2_2") (pintype "passive"))
    )
    (net (code "80") (name "Net-(IC2-OUT)") (class "Default")
      (node (ref "D2") (pin "C") (pinfunction "C_C") (pintype "passive"))
      (node (ref "IC2") (pin "2") (pinfunction "OUT_2") (pintype "output"))
      (node (ref "L1") (pin "1") (pinfunction "1_1") (pintype "passive"))
    )
    (net (code "81") (name "Net-(OK1-A)") (class "Default")
      (node (ref "OK1") (pin "1") (pinfunction "A_1") (pintype "passive"))
      (node (ref "R11") (pin "1") (pinfunction "1_1") (pintype "passive"))
    )
    (net (code "82") (name "Net-(OK1-BAS)") (class "Default")
      (node (ref "OK1") (pin "6") (pinfunction "BAS_6") (pintype "passive"))
      (node (ref "R9") (pin "1") (pinfunction "1_1") (pintype "passive"))
    )
    (net (code "83") (name "Net-(OK2-A)") (class "Default")
      (node (ref "OK2") (pin "1") (pinfunction "A_1") (pintype "passive"))
      (node (ref "R14") (pin "1") (pinfunction "1_1") (pintype "passive"))
    )
    (net (code "84") (name "Net-(OK2-BAS)") (class "Default")
      (node (ref "OK2") (pin "6") (pinfunction "BAS_6") (pintype "passive"))
      (node (ref "R10") (pin "1") (pinfunction "1_1") (pintype "passive"))
    )
    (net (code "85") (name "Net-(OK3-A)") (class "Default")
      (node (ref "OK3") (pin "1") (pinfunction "A_1") (pintype "passive"))
      (node (ref "R18") (pin "1") (pinfunction "1_1") (pintype "passive"))
    )
    (net (code "86") (name "Net-(OK3-BAS)") (class "Default")
      (node (ref "OK3") (pin "6") (pinfunction "BAS_6") (pintype "passive"))
      (node (ref "R16") (pin "1") (pinfunction "1_1") (pintype "passive"))
    )
    (net (code "87") (name "Net-(OK4-A)") (class "Default")
      (node (ref "OK4") (pin "1") (pinfunction "A_1") (pintype "passive"))
      (node (ref "R21") (pin "1") (pinfunction "1_1") (pintype "passive"))
    )
    (net (code "88") (name "Net-(OK4-BAS)") (class "Default")
      (node (ref "OK4") (pin "6") (pinfunction "BAS_6") (pintype "passive"))
      (node (ref "R20") (pin "1") (pinfunction "1_1") (pintype "passive"))
    )
    (net (code "89") (name "Net-(OK5-A)") (class "Default")
      (node (ref "OK5") (pin "1") (pinfunction "A_1") (pintype "passive"))
      (node (ref "R26") (pin "1") (pinfunction "1_1") (pintype "passive"))
    )
    (net (code "90") (name "Net-(OK5-BAS)") (class "Default")
      (node (ref "OK5") (pin "6") (pinfunction "BAS_6") (pintype "passive"))
      (node (ref "R23") (pin "1") (pinfunction "1_1") (pintype "passive"))
    )
    (net (code "91") (name "Net-(OK6-A)") (class "Default")
      (node (ref "OK6") (pin "1") (pinfunction "A_1") (pintype "passive"))
      (node (ref "R29") (pin "1") (pinfunction "1_1") (pintype "passive"))
    )
    (net (code "92") (name "Net-(OK6-BAS)") (class "Default")
      (node (ref "OK6") (pin "6") (pinfunction "BAS_6") (pintype "passive"))
      (node (ref "R28") (pin "1") (pinfunction "1_1") (pintype "passive"))
    )
    (net (code "93") (name "Net-(Q1-B)") (class "Default")
      (node (ref "Q1") (pin "1") (pinfunction "B_1") (pintype "passive"))
      (node (ref "R24") (pin "2") (pinfunction "2_2") (pintype "passive"))
    )
    (net (code "94") (name "Net-(Q2-B)") (class "Default")
      (node (ref "Q2") (pin "1") (pinfunction "B_1") (pintype "passive"))
      (node (ref "R25") (pin "2") (pinfunction "2_2") (pintype "passive"))
    )
    (net (code "95") (name "Net-(Q3-B)") (class "Default")
      (node (ref "Q3") (pin "1") (pinfunction "B_1") (pintype "passive"))
      (node (ref "R17") (pin "1") (pinfunction "1_1") (pintype "passive"))
    )
    (net (code "96") (name "Net-(Q11-B)") (class "Default")
      (node (ref "Q11") (pin "1") (pinfunction "B_1") (pintype "passive"))
      (node (ref "R32") (pin "2") (pinfunction "2_2") (pintype "passive"))
    )
    (net (code "97") (name "Net-(S1-S)") (class "Default")
      (node (ref "R54") (pin "2") (pinfunction "2_2") (pintype "passive"))
      (node (ref "S1") (pin "3") (pinfunction "S_3") (pintype "passive"))
    )
    (net (code "98") (name "Net-(S2-S)") (class "Default")
      (node (ref "R30") (pin "2") (pinfunction "2_2") (pintype "passive"))
      (node (ref "S2") (pin "3") (pinfunction "S_3") (pintype "passive"))
    )
    (net (code "99") (name "Net-(S3-S)") (class "Default")
      (node (ref "R56") (pin "2") (pinfunction "2_2") (pintype "passive"))
      (node (ref "S3") (pin "3") (pinfunction "S_3") (pintype "passive"))
    )
    (net (code "100") (name "Net-(S4-S)") (class "Default")
      (node (ref "R58") (pin "2") (pinfunction "2_2") (pintype "passive"))
      (node (ref "S4") (pin "3") (pinfunction "S_3") (pintype "passive"))
    )
    (net (code "101") (name "Net-(U$19-VIN+)") (class "Default")
      (node (ref "R6") (pin "1") (pinfunction "1_1") (pintype "passive"))
      (node (ref "R8") (pin "2") (pinfunction "2_2") (pintype "passive"))
      (node (ref "U$19") (pin "3") (pinfunction "VIN+_3") (pintype "input"))
    )
    (net (code "102") (name "Net-(U$24-VIN+)") (class "Default")
      (node (ref "R4") (pin "1") (pinfunction "1_1") (pintype "passive"))
      (node (ref "R5") (pin "2") (pinfunction "2_2") (pintype "passive"))
      (node (ref "U$24") (pin "3") (pinfunction "VIN+_3") (pintype "input"))
    )
    (net (code "103") (name "Net-(U5-COUT1)") (class "Default")
      (node (ref "R45") (pin "1") (pinfunction "1_1") (pintype "passive"))
      (node (ref "U5") (pin "4") (pinfunction "COUT1_4") (pintype "output"))
      (node (ref "U7") (pin "5") (pinfunction "2A_5") (pintype "input"))
    )
    (net (code "104") (name "Net-(U5-COUT2)") (class "Default")
      (node (ref "R44") (pin "1") (pinfunction "1_1") (pintype "passive"))
      (node (ref "U5") (pin "5") (pinfunction "COUT2_5") (pintype "output"))
      (node (ref "U7") (pin "3") (pinfunction "1A_3") (pintype "input"))
    )
    (net (code "105") (name "Net-(U6-COUT1)") (class "Default")
      (node (ref "R47") (pin "1") (pinfunction "1_1") (pintype "passive"))
      (node (ref "U6") (pin "4") (pinfunction "COUT1_4") (pintype "output"))
      (node (ref "U7") (pin "9") (pinfunction "4A_9") (pintype "input"))
    )
    (net (code "106") (name "Net-(U6-COUT2)") (class "Default")
      (node (ref "R46") (pin "1") (pinfunction "1_1") (pintype "passive"))
      (node (ref "U6") (pin "5") (pinfunction "COUT2_5") (pintype "output"))
      (node (ref "U7") (pin "7") (pinfunction "3A_7") (pintype "input"))
    )
    (net (code "107") (name "Net-(U8-CH0)") (class "Default")
      (node (ref "R54") (pin "1") (pinfunction "1_1") (pintype "passive"))
      (node (ref "R55") (pin "2") (pinfunction "2_2") (pintype "passive"))
      (node (ref "U8") (pin "1") (pinfunction "CH0_1") (pintype "input"))
    )
    (net (code "108") (name "Net-(U8-CH1)") (class "Default")
      (node (ref "R30") (pin "1") (pinfunction "1_1") (pintype "passive"))
      (node (ref "R31") (pin "2") (pinfunction "2_2") (pintype "passive"))
      (node (ref "U8") (pin "2") (pinfunction "CH1_2") (pintype "input"))
    )
    (net (code "109") (name "Net-(U8-CH2)") (class "Default")
      (node (ref "R56") (pin "1") (pinfunction "1_1") (pintype "passive"))
      (node (ref "R57") (pin "2") (pinfunction "2_2") (pintype "passive"))
      (node (ref "U8") (pin "3") (pinfunction "CH2_3") (pintype "input"))
    )
    (net (code "110") (name "Net-(U8-CH3)") (class "Default")
      (node (ref "R58") (pin "1") (pinfunction "1_1") (pintype "passive"))
      (node (ref "R59") (pin "2") (pinfunction "2_2") (pintype "passive"))
      (node (ref "U8") (pin "4") (pinfunction "CH3_4") (pintype "input"))
    )
    (net (code "111") (name "OC1") (class "Default")
      (node (ref "R11") (pin "2") (pinfunction "2_2") (pintype "passive"))
      (node (ref "U$1") (pin "P$36") (pinfunction "PC7_P$36") (pintype "bidirectional"))
    )
    (net (code "112") (name "OC2") (class "Default")
      (node (ref "R14") (pin "2") (pinfunction "2_2") (pintype "passive"))
      (node (ref "U$1") (pin "P$35") (pinfunction "PC6_P$35") (pintype "bidirectional"))
    )
    (net (code "113") (name "OC3") (class "Default")
      (node (ref "R18") (pin "2") (pinfunction "2_2") (pintype "passive"))
      (node (ref "U$1") (pin "P$38") (pinfunction "PC9_P$38") (pintype "bidirectional"))
    )
    (net (code "114") (name "OC4") (class "Default")
      (node (ref "R21") (pin "2") (pinfunction "2_2") (pintype "passive"))
      (node (ref "U$1") (pin "P$37") (pinfunction "PC8_P$37") (pintype "bidirectional"))
    )
    (net (code "115") (name "OC5") (class "Default")
      (node (ref "R26") (pin "2") (pinfunction "2_2") (pintype "passive"))
      (node (ref "U$1") (pin "P$40") (pinfunction "PA9_P$40") (pintype "bidirectional"))
    )
    (net (code "116") (name "OC6") (class "Default")
      (node (ref "R29") (pin "2") (pinfunction "2_2") (pintype "passive"))
      (node (ref "U$1") (pin "P$39") (pinfunction "PA8_P$39") (pintype "bidirectional"))
    )
    (net (code "117") (name "OILP") (class "Default")
      (node (ref "J1") (pin "C1") (pinfunction "C_C1") (pintype "bidirectional"))
      (node (ref "S1") (pin "2") (pinfunction "P_2") (pintype "passive"))
    )
    (net (code "118") (name "OILPI") (class "Default")
      (node (ref "R38") (pin "2") (pinfunction "2_2") (pintype "passive"))
      (node (ref "S1") (pin "1") (pinfunction "O_1") (pintype "passive"))
      (node (ref "U$1") (pin "P$16") (pinfunction "PE13_P$16") (pintype "bidirectional"))
    )
    (net (code "119") (name "REF") (class "Default")
      (node (ref "C15") (pin "+") (pinfunction "+_+") (pintype "passive"))
      (node (ref "U3") (pin "10") (pinfunction "REFOUT_10") (pintype "output"))
      (node (ref "U3") (pin "9") (pinfunction "REFIN_9") (pintype "input"))
    )
    (net (code "120") (name "RLY1") (class "Default")
      (node (ref "D1") (pin "C") (pinfunction "C_C") (pintype "passive"))
      (node (ref "J1") (pin "L1") (pinfunction "L_L1") (pintype "bidirectional"))
      (node (ref "OK1") (pin "5") (pinfunction "COL_5") (pintype "passive"))
    )
    (net (code "121") (name "RLY2") (class "Default")
      (node (ref "D3") (pin "C") (pinfunction "C_C") (pintype "passive"))
      (node (ref "J1") (pin "M1") (pinfunction "M_M1") (pintype "bidirectional"))
      (node (ref "OK2") (pin "5") (pinfunction "COL_5") (pintype "passive"))
    )
    (net (code "122") (name "RLY3") (class "Default")
      (node (ref "D4") (pin "C") (pinfunction "C_C") (pintype "passive"))
      (node (ref "J1") (pin "L2") (pinfunction "L_L2") (pintype "bidirectional"))
      (node (ref "OK3") (pin "5") (pinfunction "COL_5") (pintype "passive"))
    )
    (net (code "123") (name "RLY4") (class "Default")
      (node (ref "D5") (pin "C") (pinfunction "C_C") (pintype "passive"))
      (node (ref "J1") (pin "M2") (pinfunction "M_M2") (pintype "bidirectional"))
      (node (ref "OK4") (pin "5") (pinfunction "COL_5") (pintype "passive"))
    )
    (net (code "124") (name "RLY5") (class "Default")
      (node (ref "D6") (pin "C") (pinfunction "C_C") (pintype "passive"))
      (node (ref "J1") (pin "L3") (pinfunction "L_L3") (pintype "bidirectional"))
      (node (ref "OK5") (pin "5") (pinfunction "COL_5") (pintype "passive"))
    )
    (net (code "125") (name "RLY6") (class "Default")
      (node (ref "D7") (pin "C") (pinfunction "C_C") (pintype "passive"))
      (node (ref "J1") (pin "M3") (pinfunction "M_M3") (pintype "bidirectional"))
      (node (ref "OK6") (pin "5") (pinfunction "COL_5") (pintype "passive"))
    )
    (net (code "126") (name "RPM1") (class "Default")
      (node (ref "U$1") (pin "P$50") (pinfunction "PD4_P$50") (pintype "bidirectional"))
      (node (ref "U7") (pin "10") (pinfunction "4Y_10") (pintype "output"))
    )
    (net (code "127") (name "RPM1GIN") (class "Default")
      (node (ref "J2") (pin "B4") (pinfunction "B_B4") (pintype "bidirectional"))
      (node (ref "R42") (pin "1") (pinfunction "1_1") (pintype "passive"))
    )
    (net (code "128") (name "RPM1IN") (class "Default")
      (node (ref "J2") (pin "A4") (pinfunction "A_A4") (pintype "bidirectional"))
      (node (ref "R41") (pin "1") (pinfunction "1_1") (pintype "passive"))
    )
    (net (code "129") (name "RPM2") (class "Default")
      (node (ref "U$1") (pin "P$49") (pinfunction "PD3_P$49") (pintype "bidirectional"))
      (node (ref "U7") (pin "6") (pinfunction "3Y_6") (pintype "output"))
    )
    (net (code "130") (name "RPM2GIN") (class "Default")
      (node (ref "J2") (pin "B3") (pinfunction "B_B3") (pintype "bidirectional"))
      (node (ref "R27") (pin "1") (pinfunction "1_1") (pintype "passive"))
    )
    (net (code "131") (name "RPM2IN") (class "Default")
      (node (ref "J2") (pin "A3") (pinfunction "A_A3") (pintype "bidirectional"))
      (node (ref "R39") (pin "1") (pinfunction "1_1") (pintype "passive"))
    )
    (net (code "132") (name "RPM3") (class "Default")
      (node (ref "U$1") (pin "P$48") (pinfunction "PD2_P$48") (pintype "bidirectional"))
      (node (ref "U7") (pin "4") (pinfunction "2Y_4") (pintype "output"))
    )
    (net (code "133") (name "RPM3GIN") (class "Default")
      (node (ref "J2") (pin "B2") (pinfunction "B_B2") (pintype "bidirectional"))
      (node (ref "R52") (pin "1") (pinfunction "1_1") (pintype "passive"))
    )
    (net (code "134") (name "RPM3IN") (class "Default")
      (node (ref "J2") (pin "A2") (pinfunction "A_A2") (pintype "bidirectional"))
      (node (ref "R51") (pin "1") (pinfunction "1_1") (pintype "passive"))
    )
    (net (code "135") (name "RPM4") (class "Default")
      (node (ref "U$1") (pin "P$53") (pinfunction "PD7_P$53") (pintype "bidirectional"))
      (node (ref "U7") (pin "2") (pinfunction "1Y_2") (pintype "output"))
    )
    (net (code "136") (name "RPM4GIN") (class "Default")
      (node (ref "J2") (pin "B1") (pinfunction "B_B1") (pintype "bidirectional"))
      (node (ref "R48") (pin "1") (pinfunction "1_1") (pintype "passive"))
    )
    (net (code "137") (name "RPM4IN") (class "Default")
      (node (ref "J2") (pin "A1") (pinfunction "A_A1") (pintype "bidirectional"))
      (node (ref "R49") (pin "1") (pinfunction "1_1") (pintype "passive"))
    )
    (net (code "138") (name "RS232RX") (class "Default")
      (node (ref "J2") (pin "C1") (pinfunction "C_C1") (pintype "bidirectional"))
      (node (ref "U2") (pin "8") (pinfunction "R2IN_8") (pintype "input"))
    )
    (net (code "139") (name "RS232TX") (class "Default")
      (node (ref "J2") (pin "C2") (pinfunction "C_C2") (pintype "bidirectional"))
      (node (ref "U2") (pin "7") (pinfunction "T2OUT_7") (pintype "output"))
    )
    (net (code "140") (name "SCK") (class "Default")
      (node (ref "U$1") (pin "P$24") (pinfunction "PB13_P$24") (pintype "bidirectional"))
      (node (ref "U3") (pin "4") (pinfunction "SCLK_4") (pintype "input"))
      (node (ref "U8") (pin "11") (pinfunction "CLK_11") (pintype "input"))
    )
    (net (code "141") (name "SCL") (class "Default")
      (node (ref "U$1") (pin "P$58") (pinfunction "PB8_P$58") (pintype "bidirectional"))
    )
    (net (code "142") (name "SDA") (class "Default")
      (node (ref "U$1") (pin "P$57") (pinfunction "PB7_P$57") (pintype "bidirectional"))
    )
    (net (code "143") (name "SPEED") (class "Default")
      (node (ref "J2") (pin "J3") (pinfunction "J_J3") (pintype "bidirectional"))
      (node (ref "U$33") (pin "3") (pinfunction "VIN+_3") (pintype "input"))
    )
    (net (code "144") (name "SPEEDB") (class "Default")
      (node (ref "U$1") (pin "P$77") (pinfunction "PA2_P$77") (pintype "bidirectional"))
      (node (ref "U$33") (pin "1") (pinfunction "VOUT_1") (pintype "output"))
      (node (ref "U$33") (pin "4") (pinfunction "VIN-_4") (pintype "input"))
    )
    (net (code "145") (name "TRAVEL1") (class "Default")
      (node (ref "J2") (pin "L3") (pinfunction "L_L3") (pintype "bidirectional"))
      (node (ref "U$30") (pin "3") (pinfunction "VIN+_3") (pintype "input"))
    )
    (net (code "146") (name "TRAVEL1B") (class "Default")
      (node (ref "U$1") (pin "P$1") (pinfunction "PA3_P$1") (pintype "bidirectional"))
      (node (ref "U$30") (pin "1") (pinfunction "VOUT_1") (pintype "output"))
      (node (ref "U$30") (pin "4") (pinfunction "VIN-_4") (pintype "input"))
    )
    (net (code "147") (name "TRAVEL2") (class "Default")
      (node (ref "J2") (pin "L4") (pinfunction "L_L4") (pintype "bidirectional"))
      (node (ref "U$34") (pin "3") (pinfunction "VIN+_3") (pintype "input"))
    )
    (net (code "148") (name "TRAVEL2B") (class "Default")
      (node (ref "U$1") (pin "P$2") (pinfunction "PA4_P$2") (pintype "bidirectional"))
      (node (ref "U$34") (pin "1") (pinfunction "VOUT_1") (pintype "output"))
      (node (ref "U$34") (pin "4") (pinfunction "VIN-_4") (pintype "input"))
    )
    (net (code "149") (name "TRAVEL3") (class "Default")
      (node (ref "J2") (pin "L2") (pinfunction "L_L2") (pintype "bidirectional"))
      (node (ref "U$37") (pin "3") (pinfunction "VIN+_3") (pintype "input"))
    )
    (net (code "150") (name "TRAVEL3B") (class "Default")
      (node (ref "U$1") (pin "P$3") (pinfunction "PA5_P$3") (pintype "bidirectional"))
      (node (ref "U$37") (pin "1") (pinfunction "VOUT_1") (pintype "output"))
      (node (ref "U$37") (pin "4") (pinfunction "VIN-_4") (pintype "input"))
    )
    (net (code "151") (name "TRAVEL4") (class "Default")
      (node (ref "J2") (pin "L1") (pinfunction "L_L1") (pintype "bidirectional"))
      (node (ref "U$40") (pin "3") (pinfunction "VIN+_3") (pintype "input"))
    )
    (net (code "152") (name "TRAVEL4B") (class "Default")
      (node (ref "U$1") (pin "P$4") (pinfunction "PA6_P$4") (pintype "bidirectional"))
      (node (ref "U$40") (pin "1") (pinfunction "VOUT_1") (pintype "output"))
      (node (ref "U$40") (pin "4") (pinfunction "VIN-_4") (pintype "input"))
    )
    (net (code "153") (name "VCC") (class "Default")
      (node (ref "J1") (pin "L4") (pinfunction "L_L4") (pintype "bidirectional"))
      (node (ref "PTC2") (pin "P$2") (pinfunction "2_P$2") (pintype "passive"))
    )
    (net (code "154") (name "VOUT") (class "Default")
      (node (ref "J1") (pin "H3") (pinfunction "H_H3") (pintype "bidirectional"))
      (node (ref "U3") (pin "12") (pinfunction "VOUT_12") (pintype "output"))
      (node (ref "U3") (pin "14") (pinfunction "RFB_14") (pintype "passive"))
    )
    (net (code "155") (name "VTEMP") (class "Default")
      (node (ref "J2") (pin "F1") (pinfunction "F_F1") (pintype "bidirectional"))
      (node (ref "R13") (pin "2") (pinfunction "2_2") (pintype "passive"))
      (node (ref "U$45") (pin "3") (pinfunction "VIN+_3") (pintype "input"))
    )
    (net (code "156") (name "VTEMP2") (class "Default")
      (node (ref "J2") (pin "F3") (pinfunction "F_F3") (pintype "bidirectional"))
      (node (ref "R12") (pin "2") (pinfunction "2_2") (pintype "passive"))
      (node (ref "U$47") (pin "3") (pinfunction "VIN+_3") (pintype "input"))
    )
    (net (code "157") (name "VTEMP2B") (class "Default")
      (node (ref "U$1") (pin "P$74") (pinfunction "PC3_P$74") (pintype "bidirectional"))
      (node (ref "U$47") (pin "1") (pinfunction "VOUT_1") (pintype "output"))
      (node (ref "U$47") (pin "4") (pinfunction "VIN-_4") (pintype "input"))
    )
    (net (code "158") (name "VTEMPB") (class "Default")
      (node (ref "U$1") (pin "P$73") (pinfunction "PC2_P$73") (pintype "bidirectional"))
      (node (ref "U$45") (pin "1") (pinfunction "VOUT_1") (pintype "output"))
      (node (ref "U$45") (pin "4") (pinfunction "VIN-_4") (pintype "input"))
    )
    (net (code "159") (name "YAW") (class "Default")
      (node (ref "J1") (pin "A3") (pinfunction "A_A3") (pintype "bidirectional"))
      (node (ref "R6") (pin "2") (pinfunction "2_2") (pintype "passive"))
    )
    (net (code "160") (name "YAWO") (class "Default")
      (node (ref "R34") (pin "1") (pinfunction "1_1") (pintype "passive"))
      (node (ref "U$1") (pin "P$6") (pinfunction "PC4_P$6") (pintype "bidirectional"))
      (node (ref "U$19") (pin "1") (pinfunction "VOUT_1") (pintype "output"))
      (node (ref "U$19") (pin "4") (pinfunction "VIN-_4") (pintype "input"))
    )
    (net (code "161") (name "unconnected-(J1B-H-PadH2)") (class "Default")
      (node (ref "J1") (pin "H2") (pinfunction "H_H2") (pintype "bidirectional"))
    )
    (net (code "162") (name "unconnected-(J1B-K-PadK2)") (class "Default")
      (node (ref "J1") (pin "K2") (pinfunction "K_K2") (pintype "bidirectional"))
    )
    (net (code "163") (name "unconnected-(U$1B-PD8-PadP$27)") (class "Default")
      (node (ref "U$1") (pin "P$27") (pinfunction "PD8_P$27") (pintype "bidirectional"))
    )
    (net (code "164") (name "unconnected-(U$1C-PB4-PadP$54)") (class "Default")
      (node (ref "U$1") (pin "P$54") (pinfunction "PB4_P$54") (pintype "bidirectional"))
    )
    (net (code "165") (name "unconnected-(U$1C-PB9-PadP$59)") (class "Default")
      (node (ref "U$1") (pin "P$59") (pinfunction "PB9_P$59") (pintype "bidirectional"))
    )
    (net (code "166") (name "unconnected-(U$1C-PC10-PadP$45)") (class "Default")
      (node (ref "U$1") (pin "P$45") (pinfunction "PC10_P$45") (pintype "bidirectional"))
    )
    (net (code "167") (name "unconnected-(U$1C-PC11-PadP$46)") (class "Default")
      (node (ref "U$1") (pin "P$46") (pinfunction "PC11_P$46") (pintype "bidirectional"))
    )
    (net (code "168") (name "unconnected-(U$1C-PC12-PadP$47)") (class "Default")
      (node (ref "U$1") (pin "P$47") (pinfunction "PC12_P$47") (pintype "bidirectional"))
    )
    (net (code "169") (name "unconnected-(U$1C-PE0-PadP$60)") (class "Default")
      (node (ref "U$1") (pin "P$60") (pinfunction "PE0_P$60") (pintype "bidirectional"))
    )
    (net (code "170") (name "unconnected-(U$1C-PE1-PadP$61)") (class "Default")
      (node (ref "U$1") (pin "P$61") (pinfunction "PE1_P$61") (pintype "bidirectional"))
    )
    (net (code "171") (name "unconnected-(U$1D-PC1-PadP$72)") (class "Default")
      (node (ref "U$1") (pin "P$72") (pinfunction "PC1_P$72") (pintype "bidirectional"))
    )
    (net (code "172") (name "unconnected-(U$1D-PE2-PadP$63)") (class "Default")
      (node (ref "U$1") (pin "P$63") (pinfunction "PE2_P$63") (pintype "bidirectional"))
    )
    (net (code "173") (name "unconnected-(U$1D-PE3-PadP$64)") (class "Default")
      (node (ref "U$1") (pin "P$64") (pinfunction "PE3_P$64") (pintype "bidirectional"))
    )
    (net (code "174") (name "unconnected-(U2-R1IN-Pad13)") (class "Default")
      (node (ref "U2") (pin "13") (pinfunction "R1IN_13") (pintype "input"))
    )
    (net (code "175") (name "unconnected-(U2-R1OUT-Pad12)") (class "Default")
      (node (ref "U2") (pin "12") (pinfunction "R1OUT_12") (pintype "output"))
    )
    (net (code "176") (name "unconnected-(U2-T1IN-Pad11)") (class "Default")
      (node (ref "U2") (pin "11") (pinfunction "T1IN_11") (pintype "input"))
    )
    (net (code "177") (name "unconnected-(U2-T1OUT-Pad14)") (class "Default")
      (node (ref "U2") (pin "14") (pinfunction "T1OUT_14") (pintype "output"))
    )
    (net (code "178") (name "unconnected-(U4-A7-Pad8)") (class "Default")
      (node (ref "U4") (pin "8") (pinfunction "A7_8") (pintype "bidirectional"))
    )
    (net (code "179") (name "unconnected-(U4-A8-Pad9)") (class "Default")
      (node (ref "U4") (pin "9") (pinfunction "A8_9") (pintype "bidirectional"))
    )
    (net (code "180") (name "unconnected-(U4-B7-Pad13)") (class "Default")
      (node (ref "U4") (pin "13") (pinfunction "B7_13") (pintype "bidirectional"))
    )
    (net (code "181") (name "unconnected-(U4-B8-Pad12)") (class "Default")
      (node (ref "U4") (pin "12") (pinfunction "B8_12") (pintype "bidirectional"))
    )
    (net (code "182") (name "unconnected-(U5-EXT1-Pad2)") (class "Default")
      (node (ref "U5") (pin "2") (pinfunction "EXT1_2") (pintype "input"))
    )
    (net (code "183") (name "unconnected-(U5-EXT2-Pad7)") (class "Default")
      (node (ref "U5") (pin "7") (pinfunction "EXT2_7") (pintype "input"))
    )
    (net (code "184") (name "unconnected-(U5-OUT2-Pad12)") (class "Default")
      (node (ref "U5") (pin "12") (pinfunction "OUT2_12") (pintype "output"))
    )
    (net (code "185") (name "unconnected-(U6-EXT1-Pad2)") (class "Default")
      (node (ref "U6") (pin "2") (pinfunction "EXT1_2") (pintype "input"))
    )
    (net (code "186") (name "unconnected-(U6-EXT2-Pad7)") (class "Default")
      (node (ref "U6") (pin "7") (pinfunction "EXT2_7") (pintype "input"))
    )
    (net (code "187") (name "unconnected-(U6-OUT2-Pad12)") (class "Default")
      (node (ref "U6") (pin "12") (pinfunction "OUT2_12") (pintype "output"))
    )
    (net (code "188") (name "unconnected-(U7-5A-Pad11)") (class "Default")
      (node (ref "U7") (pin "11") (pinfunction "5A_11") (pintype "input"))
    )
    (net (code "189") (name "unconnected-(U7-5Y-Pad12)") (class "Default")
      (node (ref "U7") (pin "12") (pinfunction "5Y_12") (pintype "output"))
    )
    (net (code "190") (name "unconnected-(U7-6A-Pad14)") (class "Default")
      (node (ref "U7") (pin "14") (pinfunction "6A_14") (pintype "input"))
    )
    (net (code "191") (name "unconnected-(U7-6Y-Pad15)") (class "Default")
      (node (ref "U7") (pin "15") (pinfunction "6Y_15") (pintype "output"))
    )
    (net (code "192") (name "unconnected-(U7-N.C.-Pad13)") (class "Default")
      (node (ref "U7") (pin "13") (pinfunction "N.C._13") (pintype "no_connect"))
    )
    (net (code "193") (name "unconnected-(U7-N.C._2-Pad16)") (class "Default")
      (node (ref "U7") (pin "16") (pinfunction "N.C._2_16") (pintype "no_connect"))
    )
    (net (code "194") (name "unconnected-(U8-NC-Pad6)") (class "Default")
      (node (ref "U8") (pin "6") (pinfunction "NC_6") (pintype "no_connect"))
    )
    (net (code "195") (name "unconnected-(U8-NC_2-Pad5)") (class "Default")
      (node (ref "U8") (pin "5") (pinfunction "NC_2_5") (pintype "no_connect"))
    )
  )
)
